# hyperion-rev2.net
KiCad netlist of a schematic drawn in EAGLE
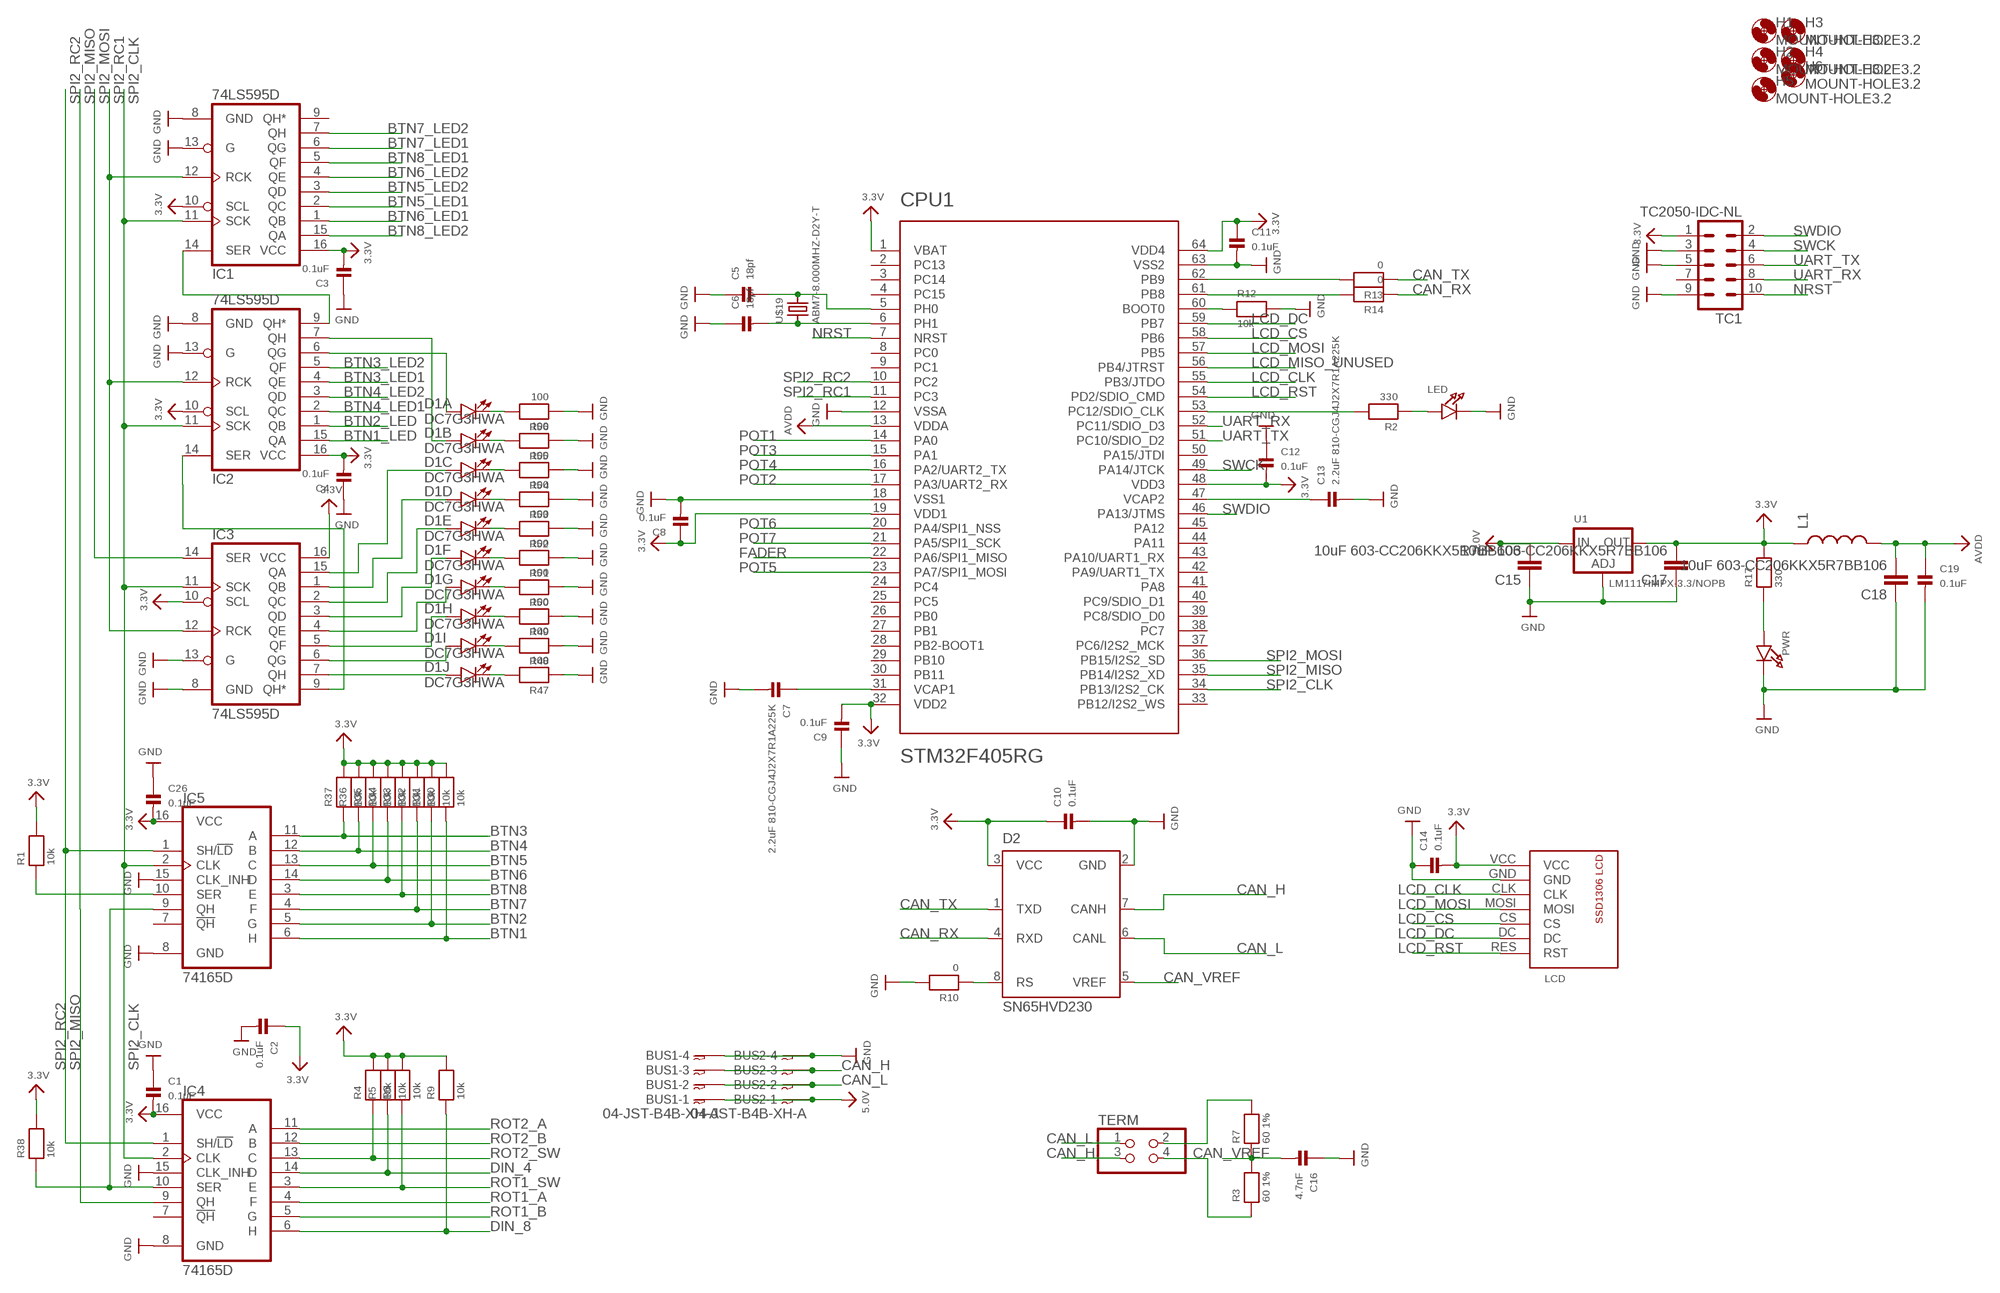
[diagram p0: schematic, sheet 1]
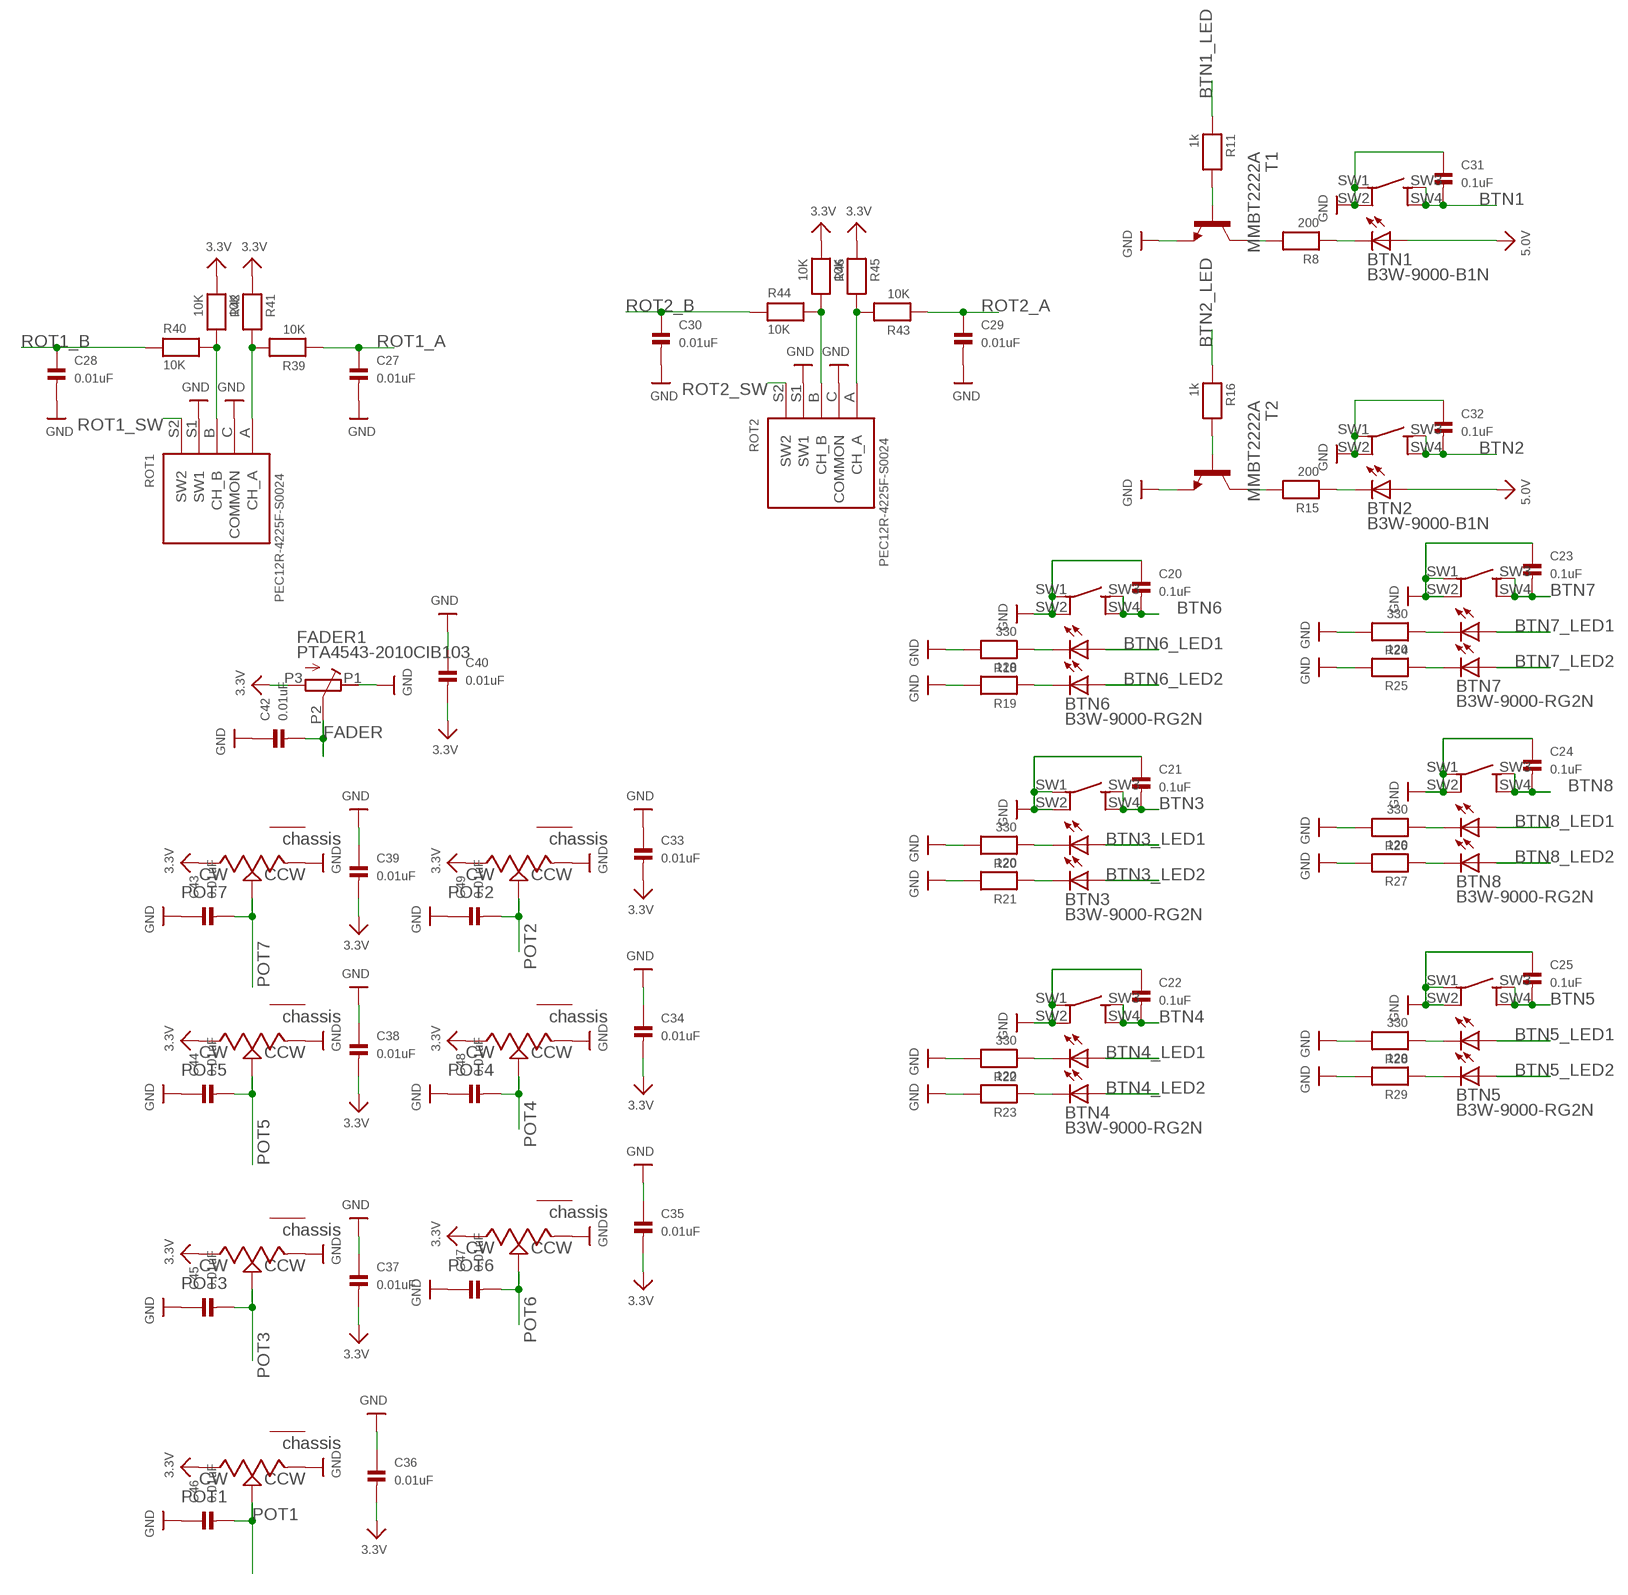
[diagram p1: schematic, sheet 2]

(export (version "E")
  (design (tool "Eeschema 10.0.6"))
  (components
    (comp (ref "BUS1")
      (value "04-JST-B4B-XH-A")
      (footprint "eagle-import:B4B-XH")
      (fields (field (name "MPN") "B4B-XH-A(LF)(SN)"))
      (libsource (lib "eagle-import") (part "04-JST-B4B-XH-A"))
    )
    (comp (ref "BUS2")
      (value "04-JST-B4B-XH-A")
      (footprint "eagle-import:B4B-XH")
      (fields (field (name "MPN") "B4B-XH-A(LF)(SN)"))
      (libsource (lib "eagle-import") (part "04-JST-B4B-XH-A"))
    )
    (comp (ref "C1")
      (value "0.1uF")
      (footprint "eagle-import:0603")
      (libsource (lib "eagle-import") (part "CAP_CERAMIC0603"))
    )
    (comp (ref "C2")
      (value "0.1uF")
      (footprint "eagle-import:0603")
      (libsource (lib "eagle-import") (part "CAP_CERAMIC0603"))
    )
    (comp (ref "C3")
      (value "0.1uF")
      (footprint "eagle-import:0603")
      (libsource (lib "eagle-import") (part "CAP_CERAMIC0603"))
    )
    (comp (ref "C4")
      (value "0.1uF")
      (footprint "eagle-import:0603")
      (libsource (lib "eagle-import") (part "CAP_CERAMIC0603"))
    )
    (comp (ref "C5")
      (value "18pf")
      (footprint "eagle-import:0603")
      (libsource (lib "eagle-import") (part "CAP_CERAMIC0603"))
    )
    (comp (ref "C6")
      (value "18pf")
      (footprint "eagle-import:0603")
      (libsource (lib "eagle-import") (part "CAP_CERAMIC0603"))
    )
    (comp (ref "C7")
      (value "2.2uF 810-CGJ4J2X7R1A225K")
      (footprint "eagle-import:0805")
      (fields (field (name "MPN") "CGJ4J2X7R1A225K125AA"))
      (libsource (lib "eagle-import") (part "CAP_CERAMIC0805"))
    )
    (comp (ref "C8")
      (value "0.1uF")
      (footprint "eagle-import:0603")
      (libsource (lib "eagle-import") (part "CAP_CERAMIC0603"))
    )
    (comp (ref "C9")
      (value "0.1uF")
      (footprint "eagle-import:0603")
      (libsource (lib "eagle-import") (part "CAP_CERAMIC0603"))
    )
    (comp (ref "C10")
      (value "0.1uF")
      (footprint "eagle-import:0603")
      (libsource (lib "eagle-import") (part "CAP_CERAMIC0603"))
    )
    (comp (ref "C11")
      (value "0.1uF")
      (footprint "eagle-import:0603")
      (libsource (lib "eagle-import") (part "CAP_CERAMIC0603"))
    )
    (comp (ref "C12")
      (value "0.1uF")
      (footprint "eagle-import:0603")
      (libsource (lib "eagle-import") (part "CAP_CERAMIC0603"))
    )
    (comp (ref "C13")
      (value "2.2uF 810-CGJ4J2X7R1A225K")
      (footprint "eagle-import:0805")
      (fields (field (name "MPN") "CGJ4J2X7R1A225K125AA"))
      (libsource (lib "eagle-import") (part "CAP_CERAMIC0805"))
    )
    (comp (ref "C14")
      (value "0.1uF")
      (footprint "eagle-import:0603")
      (libsource (lib "eagle-import") (part "CAP_CERAMIC0603"))
    )
    (comp (ref "C15")
      (value "10uF 603-CC206KKX5R7BB106")
      (footprint "eagle-import:1206")
      (fields (field (name "MPN") "CC1206KKX5R7BB106"))
      (libsource (lib "eagle-import") (part "CAP1206"))
    )
    (comp (ref "C16")
      (value "4.7nF")
      (footprint "eagle-import:0603")
      (libsource (lib "eagle-import") (part "CAP_CERAMIC0603"))
    )
    (comp (ref "C17")
      (value "10uF 603-CC206KKX5R7BB106")
      (footprint "eagle-import:1206")
      (fields (field (name "MPN") "CC1206KKX5R7BB106"))
      (libsource (lib "eagle-import") (part "CAP1206"))
    )
    (comp (ref "C18")
      (value "10uF 603-CC206KKX5R7BB106")
      (footprint "eagle-import:1206")
      (fields (field (name "MPN") "CC1206KKX5R7BB106"))
      (libsource (lib "eagle-import") (part "CAP1206"))
    )
    (comp (ref "C19")
      (value "0.1uF")
      (footprint "eagle-import:0603")
      (libsource (lib "eagle-import") (part "CAP_CERAMIC0603"))
    )
    (comp (ref "C26")
      (value "0.1uF")
      (footprint "eagle-import:0603")
      (libsource (lib "eagle-import") (part "CAP_CERAMIC0603"))
    )
    (comp (ref "CPU1")
      (value "STM32F405RG")
      (footprint "eagle-import:TQFP64")
      (fields (field (name "MPN") "STM32F405RGT6"))
      (libsource (lib "eagle-import") (part "STM32F405RG"))
    )
    (comp (ref "D1")
      (value "DC7G3HWA")
      (footprint "eagle-import:LED_BARGAPH_10")
      (libsource (lib "eagle-import") (part "LED_BARGRAPH_10"))
    )
    (comp (ref "D2")
      (value "SN65HVD230")
      (footprint "eagle-import:SO8")
      (fields (field (name "MPN") "SN65HVD230DR"))
      (libsource (lib "eagle-import") (part "SN65HVD230"))
    )
    (comp (ref "H1")
      (value "MOUNT-HOLE3.2")
      (footprint "eagle-import:3,2")
      (libsource (lib "eagle-import") (part "MOUNT-HOLE3.2"))
    )
    (comp (ref "H2")
      (value "MOUNT-HOLE3.2")
      (footprint "eagle-import:3,2")
      (libsource (lib "eagle-import") (part "MOUNT-HOLE3.2"))
    )
    (comp (ref "H3")
      (value "MOUNT-HOLE3.2")
      (footprint "eagle-import:3,2")
      (libsource (lib "eagle-import") (part "MOUNT-HOLE3.2"))
    )
    (comp (ref "H4")
      (value "MOUNT-HOLE3.2")
      (footprint "eagle-import:3,2")
      (libsource (lib "eagle-import") (part "MOUNT-HOLE3.2"))
    )
    (comp (ref "H5")
      (value "MOUNT-HOLE3.2")
      (footprint "eagle-import:3,2")
      (libsource (lib "eagle-import") (part "MOUNT-HOLE3.2"))
    )
    (comp (ref "H6")
      (value "MOUNT-HOLE3.2")
      (footprint "eagle-import:3,2")
      (libsource (lib "eagle-import") (part "MOUNT-HOLE3.2"))
    )
    (comp (ref "IC1")
      (value "74LS595D")
      (footprint "eagle-import:SO16")
      (fields (field (name "MPN") "74HC595D,118"))
      (libsource (lib "eagle-import") (part "74595DLS"))
    )
    (comp (ref "IC2")
      (value "74LS595D")
      (footprint "eagle-import:SO16")
      (fields (field (name "MPN") "74HC595D,118"))
      (libsource (lib "eagle-import") (part "74595DLS"))
    )
    (comp (ref "IC3")
      (value "74LS595D")
      (footprint "eagle-import:SO16")
      (fields (field (name "MPN") "74HC595D,118"))
      (libsource (lib "eagle-import") (part "74595DLS"))
    )
    (comp (ref "IC4")
      (value "74165D")
      (footprint "eagle-import:SO16")
      (fields (field (name "MPN") "74HC165D,653"))
      (libsource (lib "eagle-import") (part "74165D"))
    )
    (comp (ref "IC5")
      (value "74165D")
      (footprint "eagle-import:SO16")
      (fields (field (name "MPN") "74HC165D,653"))
      (libsource (lib "eagle-import") (part "74165D"))
    )
    (comp (ref "L1")
      (value "INDUCTOR0805")
      (footprint "eagle-import:0805")
      (fields (field (name "MPN") "2508056017Y2"))
      (libsource (lib "eagle-import") (part "INDUCTOR0805"))
    )
    (comp (ref "LCD")
      (value "SSD1306-7PINWITHOUT-HOLES")
      (footprint "eagle-import:SSD1306-7PIN-NO-HOLES")
      (libsource (lib "eagle-import") (part "SSD1306-7PINWITHOUT-HOLES"))
    )
    (comp (ref "LED")
      (value "LED0603")
      (footprint "eagle-import:CHIPLED_0603")
      (fields (field (name "MPN") "MF-LED-0603-GREEN"))
      (libsource (lib "eagle-import") (part "LED0603"))
    )
    (comp (ref "PWR")
      (value "LED0603")
      (footprint "eagle-import:CHIPLED_0603")
      (fields (field (name "MPN") "MF-LED-0603-GREEN"))
      (libsource (lib "eagle-import") (part "LED0603"))
    )
    (comp (ref "R1")
      (value "10k")
      (footprint "eagle-import:_0603")
      (libsource (lib "eagle-import") (part "RESISTOR_0603"))
    )
    (comp (ref "R2")
      (value "330")
      (footprint "eagle-import:0603")
      (libsource (lib "eagle-import") (part "RESISTOR0603"))
    )
    (comp (ref "R3")
      (value "60 1%")
      (footprint "eagle-import:0603")
      (fields (field (name "MPN") "MF-RES-0603-60.4"))
      (libsource (lib "eagle-import") (part "RESISTOR0603"))
    )
    (comp (ref "R4")
      (value "10k")
      (footprint "eagle-import:_0603")
      (libsource (lib "eagle-import") (part "RESISTOR_0603"))
    )
    (comp (ref "R5")
      (value "10k")
      (footprint "eagle-import:_0603")
      (libsource (lib "eagle-import") (part "RESISTOR_0603"))
    )
    (comp (ref "R6")
      (value "10k")
      (footprint "eagle-import:_0603")
      (libsource (lib "eagle-import") (part "RESISTOR_0603"))
    )
    (comp (ref "R7")
      (value "60 1%")
      (footprint "eagle-import:0603")
      (fields (field (name "MPN") "MF-RES-0603-60.4"))
      (libsource (lib "eagle-import") (part "RESISTOR0603"))
    )
    (comp (ref "R9")
      (value "10k")
      (footprint "eagle-import:_0603")
      (libsource (lib "eagle-import") (part "RESISTOR_0603"))
    )
    (comp (ref "R10")
      (value "0")
      (footprint "eagle-import:_0603")
      (libsource (lib "eagle-import") (part "RESISTOR_0603"))
    )
    (comp (ref "R12")
      (value "10k")
      (footprint "eagle-import:_0603")
      (libsource (lib "eagle-import") (part "RESISTOR_0603"))
    )
    (comp (ref "R13")
      (value "0")
      (footprint "eagle-import:_0603")
      (libsource (lib "eagle-import") (part "RESISTOR_0603"))
    )
    (comp (ref "R14")
      (value "0")
      (footprint "eagle-import:_0603")
      (libsource (lib "eagle-import") (part "RESISTOR_0603"))
    )
    (comp (ref "R17")
      (value "330")
      (footprint "eagle-import:0603")
      (libsource (lib "eagle-import") (part "RESISTOR0603"))
    )
    (comp (ref "R30")
      (value "10k")
      (footprint "eagle-import:_0603")
      (libsource (lib "eagle-import") (part "RESISTOR_0603"))
    )
    (comp (ref "R31")
      (value "10k")
      (footprint "eagle-import:_0603")
      (libsource (lib "eagle-import") (part "RESISTOR_0603"))
    )
    (comp (ref "R32")
      (value "10k")
      (footprint "eagle-import:_0603")
      (libsource (lib "eagle-import") (part "RESISTOR_0603"))
    )
    (comp (ref "R33")
      (value "10k")
      (footprint "eagle-import:_0603")
      (libsource (lib "eagle-import") (part "RESISTOR_0603"))
    )
    (comp (ref "R34")
      (value "10k")
      (footprint "eagle-import:_0603")
      (libsource (lib "eagle-import") (part "RESISTOR_0603"))
    )
    (comp (ref "R35")
      (value "10k")
      (footprint "eagle-import:_0603")
      (libsource (lib "eagle-import") (part "RESISTOR_0603"))
    )
    (comp (ref "R36")
      (value "10k")
      (footprint "eagle-import:_0603")
      (libsource (lib "eagle-import") (part "RESISTOR_0603"))
    )
    (comp (ref "R37")
      (value "10k")
      (footprint "eagle-import:_0603")
      (libsource (lib "eagle-import") (part "RESISTOR_0603"))
    )
    (comp (ref "R38")
      (value "10k")
      (footprint "eagle-import:_0603")
      (libsource (lib "eagle-import") (part "RESISTOR_0603"))
    )
    (comp (ref "R47")
      (value "100")
      (footprint "eagle-import:_0603")
      (libsource (lib "eagle-import") (part "RESISTOR_0603"))
    )
    (comp (ref "R48")
      (value "100")
      (footprint "eagle-import:_0603")
      (libsource (lib "eagle-import") (part "RESISTOR_0603"))
    )
    (comp (ref "R49")
      (value "100")
      (footprint "eagle-import:_0603")
      (libsource (lib "eagle-import") (part "RESISTOR_0603"))
    )
    (comp (ref "R50")
      (value "100")
      (footprint "eagle-import:_0603")
      (libsource (lib "eagle-import") (part "RESISTOR_0603"))
    )
    (comp (ref "R51")
      (value "100")
      (footprint "eagle-import:_0603")
      (libsource (lib "eagle-import") (part "RESISTOR_0603"))
    )
    (comp (ref "R52")
      (value "100")
      (footprint "eagle-import:_0603")
      (libsource (lib "eagle-import") (part "RESISTOR_0603"))
    )
    (comp (ref "R53")
      (value "100")
      (footprint "eagle-import:_0603")
      (libsource (lib "eagle-import") (part "RESISTOR_0603"))
    )
    (comp (ref "R54")
      (value "100")
      (footprint "eagle-import:_0603")
      (libsource (lib "eagle-import") (part "RESISTOR_0603"))
    )
    (comp (ref "R55")
      (value "100")
      (footprint "eagle-import:_0603")
      (libsource (lib "eagle-import") (part "RESISTOR_0603"))
    )
    (comp (ref "R56")
      (value "100")
      (footprint "eagle-import:_0603")
      (libsource (lib "eagle-import") (part "RESISTOR_0603"))
    )
    (comp (ref "TC1")
      (value "TC2050-IDC-NL")
      (footprint "eagle-import:TC2050-IDC-NL")
      (libsource (lib "eagle-import") (part "TC2050-IDC-NL"))
    )
    (comp (ref "TERM")
      (value "PINHD-2X2")
      (footprint "eagle-import:2X02")
      (fields (field (name "MPN") "5-146254-2"))
      (libsource (lib "eagle-import") (part "PINHD-2X2"))
    )
    (comp (ref "U$19")
      (value "ABM7-8.000MHZ-D2Y-T")
      (footprint "eagle-import:ABM7-8.000MHZ-D2Y-T")
      (libsource (lib "eagle-import") (part "ABM7-8.000MHZ-D2Y-T"))
    )
    (comp (ref "U1")
      (value "LM1117IMPX-3.3/NOPB")
      (footprint "eagle-import:SOT223-R")
      (fields (field (name "MPN") "LM1117MPX-3.3/NOPB"))
      (libsource (lib "eagle-import") (part "LM1117SOT223-REFLOW"))
    )
    (comp (ref "BTN1")
      (value "B3W-9000-B1N")
      (footprint "eagle-import:B3W-9000-X1X")
      (libsource (lib "eagle-import") (part "B3W-9000-B1N"))
    )
    (comp (ref "BTN2")
      (value "B3W-9000-B1N")
      (footprint "eagle-import:B3W-9000-X1X")
      (libsource (lib "eagle-import") (part "B3W-9000-B1N"))
    )
    (comp (ref "BTN3")
      (value "B3W-9000-RG2N")
      (footprint "eagle-import:B3W-9000-X2X")
      (libsource (lib "eagle-import") (part "B3W-9000-RG2N"))
    )
    (comp (ref "BTN4")
      (value "B3W-9000-RG2N")
      (footprint "eagle-import:B3W-9000-X2X")
      (libsource (lib "eagle-import") (part "B3W-9000-RG2N"))
    )
    (comp (ref "BTN5")
      (value "B3W-9000-RG2N")
      (footprint "eagle-import:B3W-9000-X2X")
      (libsource (lib "eagle-import") (part "B3W-9000-RG2N"))
    )
    (comp (ref "BTN6")
      (value "B3W-9000-RG2N")
      (footprint "eagle-import:B3W-9000-X2X")
      (libsource (lib "eagle-import") (part "B3W-9000-RG2N"))
    )
    (comp (ref "BTN7")
      (value "B3W-9000-RG2N")
      (footprint "eagle-import:B3W-9000-X2X")
      (libsource (lib "eagle-import") (part "B3W-9000-RG2N"))
    )
    (comp (ref "BTN8")
      (value "B3W-9000-RG2N")
      (footprint "eagle-import:B3W-9000-X2X")
      (libsource (lib "eagle-import") (part "B3W-9000-RG2N"))
    )
    (comp (ref "C20")
      (value "0.1uF")
      (footprint "eagle-import:0603")
      (libsource (lib "eagle-import") (part "CAP_CERAMIC0603"))
    )
    (comp (ref "C21")
      (value "0.1uF")
      (footprint "eagle-import:0603")
      (libsource (lib "eagle-import") (part "CAP_CERAMIC0603"))
    )
    (comp (ref "C22")
      (value "0.1uF")
      (footprint "eagle-import:0603")
      (libsource (lib "eagle-import") (part "CAP_CERAMIC0603"))
    )
    (comp (ref "C23")
      (value "0.1uF")
      (footprint "eagle-import:0603")
      (libsource (lib "eagle-import") (part "CAP_CERAMIC0603"))
    )
    (comp (ref "C24")
      (value "0.1uF")
      (footprint "eagle-import:0603")
      (libsource (lib "eagle-import") (part "CAP_CERAMIC0603"))
    )
    (comp (ref "C25")
      (value "0.1uF")
      (footprint "eagle-import:0603")
      (libsource (lib "eagle-import") (part "CAP_CERAMIC0603"))
    )
    (comp (ref "C27")
      (value "0.01uF")
      (footprint "eagle-import:0603")
      (libsource (lib "eagle-import") (part "CAP_CERAMIC0603"))
    )
    (comp (ref "C28")
      (value "0.01uF")
      (footprint "eagle-import:0603")
      (libsource (lib "eagle-import") (part "CAP_CERAMIC0603"))
    )
    (comp (ref "C29")
      (value "0.01uF")
      (footprint "eagle-import:0603")
      (libsource (lib "eagle-import") (part "CAP_CERAMIC0603"))
    )
    (comp (ref "C30")
      (value "0.01uF")
      (footprint "eagle-import:0603")
      (libsource (lib "eagle-import") (part "CAP_CERAMIC0603"))
    )
    (comp (ref "C31")
      (value "0.1uF")
      (footprint "eagle-import:0603")
      (libsource (lib "eagle-import") (part "CAP_CERAMIC0603"))
    )
    (comp (ref "C32")
      (value "0.1uF")
      (footprint "eagle-import:0603")
      (libsource (lib "eagle-import") (part "CAP_CERAMIC0603"))
    )
    (comp (ref "C33")
      (value "0.01uF")
      (footprint "eagle-import:0603")
      (libsource (lib "eagle-import") (part "CAP_CERAMIC0603"))
    )
    (comp (ref "C34")
      (value "0.01uF")
      (footprint "eagle-import:0603")
      (libsource (lib "eagle-import") (part "CAP_CERAMIC0603"))
    )
    (comp (ref "C35")
      (value "0.01uF")
      (footprint "eagle-import:0603")
      (libsource (lib "eagle-import") (part "CAP_CERAMIC0603"))
    )
    (comp (ref "C36")
      (value "0.01uF")
      (footprint "eagle-import:0603")
      (libsource (lib "eagle-import") (part "CAP_CERAMIC0603"))
    )
    (comp (ref "C37")
      (value "0.01uF")
      (footprint "eagle-import:0603")
      (libsource (lib "eagle-import") (part "CAP_CERAMIC0603"))
    )
    (comp (ref "C38")
      (value "0.01uF")
      (footprint "eagle-import:0603")
      (libsource (lib "eagle-import") (part "CAP_CERAMIC0603"))
    )
    (comp (ref "C39")
      (value "0.01uF")
      (footprint "eagle-import:0603")
      (libsource (lib "eagle-import") (part "CAP_CERAMIC0603"))
    )
    (comp (ref "C40")
      (value "0.01uF")
      (footprint "eagle-import:0603")
      (libsource (lib "eagle-import") (part "CAP_CERAMIC0603"))
    )
    (comp (ref "C42")
      (value "0.01uF")
      (footprint "eagle-import:0603")
      (libsource (lib "eagle-import") (part "CAP_CERAMIC0603"))
    )
    (comp (ref "C43")
      (value "0.01uF")
      (footprint "eagle-import:0603")
      (libsource (lib "eagle-import") (part "CAP_CERAMIC0603"))
    )
    (comp (ref "C44")
      (value "0.01uF")
      (footprint "eagle-import:0603")
      (libsource (lib "eagle-import") (part "CAP_CERAMIC0603"))
    )
    (comp (ref "C45")
      (value "0.01uF")
      (footprint "eagle-import:0603")
      (libsource (lib "eagle-import") (part "CAP_CERAMIC0603"))
    )
    (comp (ref "C46")
      (value "0.01uF")
      (footprint "eagle-import:0603")
      (libsource (lib "eagle-import") (part "CAP_CERAMIC0603"))
    )
    (comp (ref "C47")
      (value "0.01uF")
      (footprint "eagle-import:0603")
      (libsource (lib "eagle-import") (part "CAP_CERAMIC0603"))
    )
    (comp (ref "C48")
      (value "0.01uF")
      (footprint "eagle-import:0603")
      (libsource (lib "eagle-import") (part "CAP_CERAMIC0603"))
    )
    (comp (ref "C49")
      (value "0.01uF")
      (footprint "eagle-import:0603")
      (libsource (lib "eagle-import") (part "CAP_CERAMIC0603"))
    )
    (comp (ref "FADER1")
      (value "PTA4543-2010CIB103")
      (footprint "eagle-import:PTA4543-2015CPB103")
      (libsource (lib "eagle-import") (part "PTA4543-2015CPB103"))
    )
    (comp (ref "POT1")
      (value "POTENTIOMETERPTV09A_VERTICAL")
      (footprint "eagle-import:PTV09A-4")
      (fields (field (name "MPN") "PTV09A-4225F-B203"))
      (libsource (lib "eagle-import") (part "POTENTIOMETERPTV09A_VERTICAL"))
    )
    (comp (ref "POT2")
      (value "POTENTIOMETERPTV09A_VERTICAL")
      (footprint "eagle-import:PTV09A-4")
      (fields (field (name "MPN") "PTV09A-4225F-B203"))
      (libsource (lib "eagle-import") (part "POTENTIOMETERPTV09A_VERTICAL"))
    )
    (comp (ref "POT3")
      (value "POTENTIOMETERPTV09A_VERTICAL")
      (footprint "eagle-import:PTV09A-4")
      (fields (field (name "MPN") "PTV09A-4225F-B203"))
      (libsource (lib "eagle-import") (part "POTENTIOMETERPTV09A_VERTICAL"))
    )
    (comp (ref "POT4")
      (value "POTENTIOMETERPTV09A_VERTICAL")
      (footprint "eagle-import:PTV09A-4")
      (fields (field (name "MPN") "PTV09A-4225F-B203"))
      (libsource (lib "eagle-import") (part "POTENTIOMETERPTV09A_VERTICAL"))
    )
    (comp (ref "POT5")
      (value "POTENTIOMETERPTV09A_VERTICAL")
      (footprint "eagle-import:PTV09A-4")
      (fields (field (name "MPN") "PTV09A-4225F-B203"))
      (libsource (lib "eagle-import") (part "POTENTIOMETERPTV09A_VERTICAL"))
    )
    (comp (ref "POT6")
      (value "POTENTIOMETERPTV09A_VERTICAL")
      (footprint "eagle-import:PTV09A-4")
      (fields (field (name "MPN") "PTV09A-4225F-B203"))
      (libsource (lib "eagle-import") (part "POTENTIOMETERPTV09A_VERTICAL"))
    )
    (comp (ref "POT7")
      (value "POTENTIOMETERPTV09A_VERTICAL")
      (footprint "eagle-import:PTV09A-4")
      (fields (field (name "MPN") "PTV09A-4225F-B203"))
      (libsource (lib "eagle-import") (part "POTENTIOMETERPTV09A_VERTICAL"))
    )
    (comp (ref "R8")
      (value "200")
      (footprint "eagle-import:0603")
      (libsource (lib "eagle-import") (part "RESISTOR0603"))
    )
    (comp (ref "R11")
      (value "1k")
      (footprint "eagle-import:0603")
      (libsource (lib "eagle-import") (part "RESISTOR0603"))
    )
    (comp (ref "R15")
      (value "200")
      (footprint "eagle-import:0603")
      (libsource (lib "eagle-import") (part "RESISTOR0603"))
    )
    (comp (ref "R16")
      (value "1k")
      (footprint "eagle-import:0603")
      (libsource (lib "eagle-import") (part "RESISTOR0603"))
    )
    (comp (ref "R18")
      (value "330")
      (footprint "eagle-import:0603")
      (libsource (lib "eagle-import") (part "RESISTOR0603"))
    )
    (comp (ref "R19")
      (value "120")
      (footprint "eagle-import:0603")
      (libsource (lib "eagle-import") (part "RESISTOR0603"))
    )
    (comp (ref "R20")
      (value "330")
      (footprint "eagle-import:0603")
      (libsource (lib "eagle-import") (part "RESISTOR0603"))
    )
    (comp (ref "R21")
      (value "120")
      (footprint "eagle-import:0603")
      (libsource (lib "eagle-import") (part "RESISTOR0603"))
    )
    (comp (ref "R22")
      (value "330")
      (footprint "eagle-import:0603")
      (libsource (lib "eagle-import") (part "RESISTOR0603"))
    )
    (comp (ref "R23")
      (value "120")
      (footprint "eagle-import:0603")
      (libsource (lib "eagle-import") (part "RESISTOR0603"))
    )
    (comp (ref "R24")
      (value "330")
      (footprint "eagle-import:0603")
      (libsource (lib "eagle-import") (part "RESISTOR0603"))
    )
    (comp (ref "R25")
      (value "120")
      (footprint "eagle-import:0603")
      (libsource (lib "eagle-import") (part "RESISTOR0603"))
    )
    (comp (ref "R26")
      (value "330")
      (footprint "eagle-import:0603")
      (libsource (lib "eagle-import") (part "RESISTOR0603"))
    )
    (comp (ref "R27")
      (value "120")
      (footprint "eagle-import:0603")
      (libsource (lib "eagle-import") (part "RESISTOR0603"))
    )
    (comp (ref "R28")
      (value "330")
      (footprint "eagle-import:0603")
      (libsource (lib "eagle-import") (part "RESISTOR0603"))
    )
    (comp (ref "R29")
      (value "120")
      (footprint "eagle-import:0603")
      (libsource (lib "eagle-import") (part "RESISTOR0603"))
    )
    (comp (ref "R39")
      (value "10K")
      (footprint "eagle-import:0603")
      (libsource (lib "eagle-import") (part "RESISTOR0603"))
    )
    (comp (ref "R40")
      (value "10K")
      (footprint "eagle-import:0603")
      (libsource (lib "eagle-import") (part "RESISTOR0603"))
    )
    (comp (ref "R41")
      (value "10K")
      (footprint "eagle-import:0603")
      (libsource (lib "eagle-import") (part "RESISTOR0603"))
    )
    (comp (ref "R42")
      (value "10K")
      (footprint "eagle-import:0603")
      (libsource (lib "eagle-import") (part "RESISTOR0603"))
    )
    (comp (ref "R43")
      (value "10K")
      (footprint "eagle-import:0603")
      (libsource (lib "eagle-import") (part "RESISTOR0603"))
    )
    (comp (ref "R44")
      (value "10K")
      (footprint "eagle-import:0603")
      (libsource (lib "eagle-import") (part "RESISTOR0603"))
    )
    (comp (ref "R45")
      (value "10K")
      (footprint "eagle-import:0603")
      (libsource (lib "eagle-import") (part "RESISTOR0603"))
    )
    (comp (ref "R46")
      (value "10K")
      (footprint "eagle-import:0603")
      (libsource (lib "eagle-import") (part "RESISTOR0603"))
    )
    (comp (ref "ROT1")
      (value "PEC12R-4225F-S0024")
      (footprint "eagle-import:PEC111-4XXXK-SXXXX")
      (libsource (lib "eagle-import") (part "PEC11-4215K-S0024"))
    )
    (comp (ref "ROT2")
      (value "PEC12R-4225F-S0024")
      (footprint "eagle-import:PEC111-4XXXK-SXXXX")
      (libsource (lib "eagle-import") (part "PEC11-4215K-S0024"))
    )
    (comp (ref "T1")
      (value "MMBT2222A")
      (footprint "eagle-import:SOT23-BEC")
      (libsource (lib "eagle-import") (part "-NPN-SOT23-BECMMBT2222ALT1"))
    )
    (comp (ref "T2")
      (value "MMBT2222A")
      (footprint "eagle-import:SOT23-BEC")
      (libsource (lib "eagle-import") (part "-NPN-SOT23-BECMMBT2222ALT1"))
    )
  )
  (nets
    (net (code "1") (name "3.3V") (class "Default")
      (node (ref "C1") (pin "2") (pinfunction "P$2_2") (pintype "passive"))
      (node (ref "C10") (pin "1") (pinfunction "P$1_1") (pintype "passive"))
      (node (ref "C11") (pin "1") (pinfunction "P$1_1") (pintype "passive"))
      (node (ref "C12") (pin "2") (pinfunction "P$2_2") (pintype "passive"))
      (node (ref "C14") (pin "2") (pinfunction "P$2_2") (pintype "passive"))
      (node (ref "C17") (pin "2") (pinfunction "2_2") (pintype "passive"))
      (node (ref "C2") (pin "1") (pinfunction "P$1_1") (pintype "passive"))
      (node (ref "C26") (pin "2") (pinfunction "P$2_2") (pintype "passive"))
      (node (ref "C3") (pin "2") (pinfunction "P$2_2") (pintype "passive"))
      (node (ref "C33") (pin "2") (pinfunction "P$2_2") (pintype "passive"))
      (node (ref "C34") (pin "2") (pinfunction "P$2_2") (pintype "passive"))
      (node (ref "C35") (pin "2") (pinfunction "P$2_2") (pintype "passive"))
      (node (ref "C36") (pin "2") (pinfunction "P$2_2") (pintype "passive"))
      (node (ref "C37") (pin "2") (pinfunction "P$2_2") (pintype "passive"))
      (node (ref "C38") (pin "2") (pinfunction "P$2_2") (pintype "passive"))
      (node (ref "C39") (pin "2") (pinfunction "P$2_2") (pintype "passive"))
      (node (ref "C4") (pin "2") (pinfunction "P$2_2") (pintype "passive"))
      (node (ref "C40") (pin "2") (pinfunction "P$2_2") (pintype "passive"))
      (node (ref "C8") (pin "1") (pinfunction "P$1_1") (pintype "passive"))
      (node (ref "C9") (pin "2") (pinfunction "P$2_2") (pintype "passive"))
      (node (ref "CPU1") (pin "1") (pinfunction "VBAT_1") (pintype "bidirectional"))
      (node (ref "CPU1") (pin "19") (pinfunction "VDD1_19") (pintype "bidirectional"))
      (node (ref "CPU1") (pin "32") (pinfunction "VDD2_32") (pintype "bidirectional"))
      (node (ref "CPU1") (pin "48") (pinfunction "VDD3_48") (pintype "bidirectional"))
      (node (ref "CPU1") (pin "64") (pinfunction "VDD4_64") (pintype "bidirectional"))
      (node (ref "D2") (pin "3") (pinfunction "VCC_3") (pintype "power_in"))
      (node (ref "FADER1") (pin "P3") (pinfunction "E_P3") (pintype "passive"))
      (node (ref "IC1") (pin "10") (pinfunction "SCL_10") (pintype "input"))
      (node (ref "IC1") (pin "16") (pinfunction "VCC_16") (pintype "power_in"))
      (node (ref "IC2") (pin "10") (pinfunction "SCL_10") (pintype "input"))
      (node (ref "IC2") (pin "16") (pinfunction "VCC_16") (pintype "power_in"))
      (node (ref "IC3") (pin "10") (pinfunction "SCL_10") (pintype "input"))
      (node (ref "IC3") (pin "16") (pinfunction "VCC_16") (pintype "power_in"))
      (node (ref "IC4") (pin "16") (pinfunction "VCC_16") (pintype "power_in"))
      (node (ref "IC5") (pin "16") (pinfunction "VCC_16") (pintype "power_in"))
      (node (ref "L1") (pin "1") (pinfunction "1_1") (pintype "passive"))
      (node (ref "LCD") (pin "VCC") (pinfunction "VCC_VCC") (pintype "bidirectional"))
      (node (ref "POT1") (pin "CW") (pinfunction "CW_CW") (pintype "passive"))
      (node (ref "POT2") (pin "CW") (pinfunction "CW_CW") (pintype "passive"))
      (node (ref "POT3") (pin "CW") (pinfunction "CW_CW") (pintype "passive"))
      (node (ref "POT4") (pin "CW") (pinfunction "CW_CW") (pintype "passive"))
      (node (ref "POT5") (pin "CW") (pinfunction "CW_CW") (pintype "passive"))
      (node (ref "POT6") (pin "CW") (pinfunction "CW_CW") (pintype "passive"))
      (node (ref "POT7") (pin "CW") (pinfunction "CW_CW") (pintype "passive"))
      (node (ref "R1") (pin "2") (pinfunction "2_2") (pintype "passive"))
      (node (ref "R17") (pin "2") (pinfunction "2_2") (pintype "passive"))
      (node (ref "R30") (pin "2") (pinfunction "2_2") (pintype "passive"))
      (node (ref "R31") (pin "2") (pinfunction "2_2") (pintype "passive"))
      (node (ref "R32") (pin "2") (pinfunction "2_2") (pintype "passive"))
      (node (ref "R33") (pin "2") (pinfunction "2_2") (pintype "passive"))
      (node (ref "R34") (pin "2") (pinfunction "2_2") (pintype "passive"))
      (node (ref "R35") (pin "2") (pinfunction "2_2") (pintype "passive"))
      (node (ref "R36") (pin "2") (pinfunction "2_2") (pintype "passive"))
      (node (ref "R37") (pin "2") (pinfunction "2_2") (pintype "passive"))
      (node (ref "R38") (pin "2") (pinfunction "2_2") (pintype "passive"))
      (node (ref "R4") (pin "2") (pinfunction "2_2") (pintype "passive"))
      (node (ref "R41") (pin "1") (pinfunction "1_1") (pintype "passive"))
      (node (ref "R42") (pin "1") (pinfunction "1_1") (pintype "passive"))
      (node (ref "R45") (pin "1") (pinfunction "1_1") (pintype "passive"))
      (node (ref "R46") (pin "1") (pinfunction "1_1") (pintype "passive"))
      (node (ref "R5") (pin "2") (pinfunction "2_2") (pintype "passive"))
      (node (ref "R6") (pin "2") (pinfunction "2_2") (pintype "passive"))
      (node (ref "R9") (pin "2") (pinfunction "2_2") (pintype "passive"))
      (node (ref "TC1") (pin "1") (pinfunction "1_1") (pintype "passive"))
      (node (ref "U1") (pin "2") (pinfunction "OUT_2") (pintype "passive"))
    )
    (net (code "2") (name "5.0V") (class "Default")
      (node (ref "BTN1") (pin "LED1+") (pinfunction "LED1+_LED1+") (pintype "passive"))
      (node (ref "BTN2") (pin "LED1+") (pinfunction "LED1+_LED1+") (pintype "passive"))
      (node (ref "BUS1") (pin "P$1") (pinfunction "1_P$1") (pintype "passive"))
      (node (ref "BUS2") (pin "P$1") (pinfunction "1_P$1") (pintype "passive"))
      (node (ref "C15") (pin "2") (pinfunction "2_2") (pintype "passive"))
      (node (ref "U1") (pin "3") (pinfunction "IN_3") (pintype "input"))
    )
    (net (code "3") (name "AVDD") (class "Default")
      (node (ref "C18") (pin "2") (pinfunction "2_2") (pintype "passive"))
      (node (ref "C19") (pin "1") (pinfunction "P$1_1") (pintype "passive"))
      (node (ref "CPU1") (pin "13") (pinfunction "VDDA_13") (pintype "bidirectional"))
      (node (ref "L1") (pin "2") (pinfunction "2_2") (pintype "passive"))
    )
    (net (code "4") (name "BTN1") (class "Default")
      (node (ref "BTN1") (pin "SW3") (pinfunction "SW2_A_SW3") (pintype "passive"))
      (node (ref "BTN1") (pin "SW4") (pinfunction "SW2_B_SW4") (pintype "passive"))
      (node (ref "C31") (pin "2") (pinfunction "P$2_2") (pintype "passive"))
      (node (ref "IC5") (pin "6") (pinfunction "H_6") (pintype "tri_state"))
      (node (ref "R30") (pin "1") (pinfunction "1_1") (pintype "passive"))
    )
    (net (code "5") (name "BTN1_LED") (class "Default")
      (node (ref "IC2") (pin "15") (pinfunction "QA_15") (pintype "tri_state"))
      (node (ref "R11") (pin "1") (pinfunction "1_1") (pintype "passive"))
    )
    (net (code "6") (name "BTN2") (class "Default")
      (node (ref "BTN2") (pin "SW3") (pinfunction "SW2_A_SW3") (pintype "passive"))
      (node (ref "BTN2") (pin "SW4") (pinfunction "SW2_B_SW4") (pintype "passive"))
      (node (ref "C32") (pin "2") (pinfunction "P$2_2") (pintype "passive"))
      (node (ref "IC5") (pin "5") (pinfunction "G_5") (pintype "tri_state"))
      (node (ref "R31") (pin "1") (pinfunction "1_1") (pintype "passive"))
    )
    (net (code "7") (name "BTN2_LED") (class "Default")
      (node (ref "IC2") (pin "1") (pinfunction "QB_1") (pintype "tri_state"))
      (node (ref "R16") (pin "1") (pinfunction "1_1") (pintype "passive"))
    )
    (net (code "8") (name "BTN3") (class "Default")
      (node (ref "BTN3") (pin "SW3") (pinfunction "SW2_A_SW3") (pintype "passive"))
      (node (ref "BTN3") (pin "SW4") (pinfunction "SW2_B_SW4") (pintype "passive"))
      (node (ref "C21") (pin "2") (pinfunction "P$2_2") (pintype "passive"))
      (node (ref "IC5") (pin "11") (pinfunction "A_11") (pintype "tri_state"))
      (node (ref "R37") (pin "1") (pinfunction "1_1") (pintype "passive"))
    )
    (net (code "9") (name "BTN3_LED1") (class "Default")
      (node (ref "BTN3") (pin "LED1+") (pinfunction "LED1+_LED1+") (pintype "passive"))
      (node (ref "IC2") (pin "4") (pinfunction "QE_4") (pintype "tri_state"))
    )
    (net (code "10") (name "BTN3_LED2") (class "Default")
      (node (ref "BTN3") (pin "LED2+") (pinfunction "LED2+_LED2+") (pintype "passive"))
      (node (ref "IC2") (pin "5") (pinfunction "QF_5") (pintype "tri_state"))
    )
    (net (code "11") (name "BTN4") (class "Default")
      (node (ref "BTN4") (pin "SW3") (pinfunction "SW2_A_SW3") (pintype "passive"))
      (node (ref "BTN4") (pin "SW4") (pinfunction "SW2_B_SW4") (pintype "passive"))
      (node (ref "C22") (pin "2") (pinfunction "P$2_2") (pintype "passive"))
      (node (ref "IC5") (pin "12") (pinfunction "B_12") (pintype "tri_state"))
      (node (ref "R36") (pin "1") (pinfunction "1_1") (pintype "passive"))
    )
    (net (code "12") (name "BTN4_LED1") (class "Default")
      (node (ref "BTN4") (pin "LED1+") (pinfunction "LED1+_LED1+") (pintype "passive"))
      (node (ref "IC2") (pin "2") (pinfunction "QC_2") (pintype "tri_state"))
    )
    (net (code "13") (name "BTN4_LED2") (class "Default")
      (node (ref "BTN4") (pin "LED2+") (pinfunction "LED2+_LED2+") (pintype "passive"))
      (node (ref "IC2") (pin "3") (pinfunction "QD_3") (pintype "tri_state"))
    )
    (net (code "14") (name "BTN5") (class "Default")
      (node (ref "BTN5") (pin "SW3") (pinfunction "SW2_A_SW3") (pintype "passive"))
      (node (ref "BTN5") (pin "SW4") (pinfunction "SW2_B_SW4") (pintype "passive"))
      (node (ref "C25") (pin "2") (pinfunction "P$2_2") (pintype "passive"))
      (node (ref "IC5") (pin "13") (pinfunction "C_13") (pintype "tri_state"))
      (node (ref "R35") (pin "1") (pinfunction "1_1") (pintype "passive"))
    )
    (net (code "15") (name "BTN5_LED1") (class "Default")
      (node (ref "BTN5") (pin "LED1+") (pinfunction "LED1+_LED1+") (pintype "passive"))
      (node (ref "IC1") (pin "2") (pinfunction "QC_2") (pintype "tri_state"))
    )
    (net (code "16") (name "BTN5_LED2") (class "Default")
      (node (ref "BTN5") (pin "LED2+") (pinfunction "LED2+_LED2+") (pintype "passive"))
      (node (ref "IC1") (pin "3") (pinfunction "QD_3") (pintype "tri_state"))
    )
    (net (code "17") (name "BTN6") (class "Default")
      (node (ref "BTN6") (pin "SW3") (pinfunction "SW2_A_SW3") (pintype "passive"))
      (node (ref "BTN6") (pin "SW4") (pinfunction "SW2_B_SW4") (pintype "passive"))
      (node (ref "C20") (pin "2") (pinfunction "P$2_2") (pintype "passive"))
      (node (ref "IC5") (pin "14") (pinfunction "D_14") (pintype "tri_state"))
      (node (ref "R34") (pin "1") (pinfunction "1_1") (pintype "passive"))
    )
    (net (code "18") (name "BTN6_LED1") (class "Default")
      (node (ref "BTN6") (pin "LED1+") (pinfunction "LED1+_LED1+") (pintype "passive"))
      (node (ref "IC1") (pin "1") (pinfunction "QB_1") (pintype "tri_state"))
    )
    (net (code "19") (name "BTN6_LED2") (class "Default")
      (node (ref "BTN6") (pin "LED2+") (pinfunction "LED2+_LED2+") (pintype "passive"))
      (node (ref "IC1") (pin "4") (pinfunction "QE_4") (pintype "tri_state"))
    )
    (net (code "20") (name "BTN7") (class "Default")
      (node (ref "BTN7") (pin "SW3") (pinfunction "SW2_A_SW3") (pintype "passive"))
      (node (ref "BTN7") (pin "SW4") (pinfunction "SW2_B_SW4") (pintype "passive"))
      (node (ref "C23") (pin "2") (pinfunction "P$2_2") (pintype "passive"))
      (node (ref "IC5") (pin "4") (pinfunction "F_4") (pintype "tri_state"))
      (node (ref "R32") (pin "1") (pinfunction "1_1") (pintype "passive"))
    )
    (net (code "21") (name "BTN7_LED1") (class "Default")
      (node (ref "BTN7") (pin "LED1+") (pinfunction "LED1+_LED1+") (pintype "passive"))
      (node (ref "IC1") (pin "6") (pinfunction "QG_6") (pintype "tri_state"))
    )
    (net (code "22") (name "BTN7_LED2") (class "Default")
      (node (ref "BTN7") (pin "LED2+") (pinfunction "LED2+_LED2+") (pintype "passive"))
      (node (ref "IC1") (pin "7") (pinfunction "QH_7") (pintype "tri_state"))
    )
    (net (code "23") (name "BTN8") (class "Default")
      (node (ref "BTN8") (pin "SW3") (pinfunction "SW2_A_SW3") (pintype "passive"))
      (node (ref "BTN8") (pin "SW4") (pinfunction "SW2_B_SW4") (pintype "passive"))
      (node (ref "C24") (pin "2") (pinfunction "P$2_2") (pintype "passive"))
      (node (ref "IC5") (pin "3") (pinfunction "E_3") (pintype "tri_state"))
      (node (ref "R33") (pin "1") (pinfunction "1_1") (pintype "passive"))
    )
    (net (code "24") (name "BTN8_LED1") (class "Default")
      (node (ref "BTN8") (pin "LED1+") (pinfunction "LED1+_LED1+") (pintype "passive"))
      (node (ref "IC1") (pin "5") (pinfunction "QF_5") (pintype "tri_state"))
    )
    (net (code "25") (name "BTN8_LED2") (class "Default")
      (node (ref "BTN8") (pin "LED2+") (pinfunction "LED2+_LED2+") (pintype "passive"))
      (node (ref "IC1") (pin "15") (pinfunction "QA_15") (pintype "tri_state"))
    )
    (net (code "26") (name "CAN_H") (class "Default")
      (node (ref "BUS1") (pin "P$3") (pinfunction "1_P$3") (pintype "passive"))
      (node (ref "BUS2") (pin "P$3") (pinfunction "1_P$3") (pintype "passive"))
      (node (ref "D2") (pin "7") (pinfunction "CANH_7") (pintype "bidirectional"))
      (node (ref "TERM") (pin "3") (pinfunction "3_3") (pintype "passive"))
    )
    (net (code "27") (name "CAN_L") (class "Default")
      (node (ref "BUS1") (pin "P$2") (pinfunction "1_P$2") (pintype "passive"))
      (node (ref "BUS2") (pin "P$2") (pinfunction "1_P$2") (pintype "passive"))
      (node (ref "D2") (pin "6") (pinfunction "CANL_6") (pintype "bidirectional"))
      (node (ref "TERM") (pin "1") (pinfunction "1_1") (pintype "passive"))
    )
    (net (code "28") (name "CAN_RX") (class "Default")
      (node (ref "D2") (pin "4") (pinfunction "RXD_4") (pintype "output"))
      (node (ref "R14") (pin "1") (pinfunction "1_1") (pintype "passive"))
    )
    (net (code "29") (name "CAN_TX") (class "Default")
      (node (ref "D2") (pin "1") (pinfunction "TXD_1") (pintype "input"))
      (node (ref "R13") (pin "1") (pinfunction "1_1") (pintype "passive"))
    )
    (net (code "30") (name "CAN_VREF") (class "Default")
      (node (ref "C16") (pin "2") (pinfunction "P$2_2") (pintype "passive"))
      (node (ref "D2") (pin "5") (pinfunction "VREF_5") (pintype "output"))
      (node (ref "R3") (pin "2") (pinfunction "2_2") (pintype "passive"))
      (node (ref "R7") (pin "1") (pinfunction "1_1") (pintype "passive"))
    )
    (net (code "31") (name "DIN_4") (class "Default")
      (node (ref "IC4") (pin "14") (pinfunction "D_14") (pintype "tri_state"))
      (node (ref "R5") (pin "1") (pinfunction "1_1") (pintype "passive"))
    )
    (net (code "32") (name "DIN_8") (class "Default")
      (node (ref "IC4") (pin "6") (pinfunction "H_6") (pintype "tri_state"))
      (node (ref "R9") (pin "1") (pinfunction "1_1") (pintype "passive"))
    )
    (net (code "33") (name "FADER") (class "Default")
      (node (ref "C42") (pin "2") (pinfunction "P$2_2") (pintype "passive"))
      (node (ref "CPU1") (pin "22") (pinfunction "PA6/SPI1_MISO_22") (pintype "bidirectional"))
      (node (ref "FADER1") (pin "P2") (pinfunction "S_P2") (pintype "passive"))
    )
    (net (code "34") (name "GND") (class "Default")
      (node (ref "BTN1") (pin "SW1") (pinfunction "SW1_A_SW1") (pintype "passive"))
      (node (ref "BTN1") (pin "SW2") (pinfunction "SW1_B_SW2") (pintype "passive"))
      (node (ref "BTN2") (pin "SW1") (pinfunction "SW1_A_SW1") (pintype "passive"))
      (node (ref "BTN2") (pin "SW2") (pinfunction "SW1_B_SW2") (pintype "passive"))
      (node (ref "BTN3") (pin "SW1") (pinfunction "SW1_A_SW1") (pintype "passive"))
      (node (ref "BTN3") (pin "SW2") (pinfunction "SW1_B_SW2") (pintype "passive"))
      (node (ref "BTN4") (pin "SW1") (pinfunction "SW1_A_SW1") (pintype "passive"))
      (node (ref "BTN4") (pin "SW2") (pinfunction "SW1_B_SW2") (pintype "passive"))
      (node (ref "BTN5") (pin "SW1") (pinfunction "SW1_A_SW1") (pintype "passive"))
      (node (ref "BTN5") (pin "SW2") (pinfunction "SW1_B_SW2") (pintype "passive"))
      (node (ref "BTN6") (pin "SW1") (pinfunction "SW1_A_SW1") (pintype "passive"))
      (node (ref "BTN6") (pin "SW2") (pinfunction "SW1_B_SW2") (pintype "passive"))
      (node (ref "BTN7") (pin "SW1") (pinfunction "SW1_A_SW1") (pintype "passive"))
      (node (ref "BTN7") (pin "SW2") (pinfunction "SW1_B_SW2") (pintype "passive"))
      (node (ref "BTN8") (pin "SW1") (pinfunction "SW1_A_SW1") (pintype "passive"))
      (node (ref "BTN8") (pin "SW2") (pinfunction "SW1_B_SW2") (pintype "passive"))
      (node (ref "BUS1") (pin "P$4") (pinfunction "1_P$4") (pintype "passive"))
      (node (ref "BUS2") (pin "P$4") (pinfunction "1_P$4") (pintype "passive"))
      (node (ref "C1") (pin "1") (pinfunction "P$1_1") (pintype "passive"))
      (node (ref "C10") (pin "2") (pinfunction "P$2_2") (pintype "passive"))
      (node (ref "C11") (pin "2") (pinfunction "P$2_2") (pintype "passive"))
      (node (ref "C12") (pin "1") (pinfunction "P$1_1") (pintype "passive"))
      (node (ref "C13") (pin "2") (pinfunction "P$2_2") (pintype "passive"))
      (node (ref "C14") (pin "1") (pinfunction "P$1_1") (pintype "passive"))
      (node (ref "C15") (pin "1") (pinfunction "1_1") (pintype "passive"))
      (node (ref "C16") (pin "1") (pinfunction "P$1_1") (pintype "passive"))
      (node (ref "C17") (pin "1") (pinfunction "1_1") (pintype "passive"))
      (node (ref "C18") (pin "1") (pinfunction "1_1") (pintype "passive"))
      (node (ref "C19") (pin "2") (pinfunction "P$2_2") (pintype "passive"))
      (node (ref "C2") (pin "2") (pinfunction "P$2_2") (pintype "passive"))
      (node (ref "C20") (pin "1") (pinfunction "P$1_1") (pintype "passive"))
      (node (ref "C21") (pin "1") (pinfunction "P$1_1") (pintype "passive"))
      (node (ref "C22") (pin "1") (pinfunction "P$1_1") (pintype "passive"))
      (node (ref "C23") (pin "1") (pinfunction "P$1_1") (pintype "passive"))
      (node (ref "C24") (pin "1") (pinfunction "P$1_1") (pintype "passive"))
      (node (ref "C25") (pin "1") (pinfunction "P$1_1") (pintype "passive"))
      (node (ref "C26") (pin "1") (pinfunction "P$1_1") (pintype "passive"))
      (node (ref "C27") (pin "2") (pinfunction "P$2_2") (pintype "passive"))
      (node (ref "C28") (pin "2") (pinfunction "P$2_2") (pintype "passive"))
      (node (ref "C29") (pin "2") (pinfunction "P$2_2") (pintype "passive"))
      (node (ref "C3") (pin "1") (pinfunction "P$1_1") (pintype "passive"))
      (node (ref "C30") (pin "2") (pinfunction "P$2_2") (pintype "passive"))
      (node (ref "C31") (pin "1") (pinfunction "P$1_1") (pintype "passive"))
      (node (ref "C32") (pin "1") (pinfunction "P$1_1") (pintype "passive"))
      (node (ref "C33") (pin "1") (pinfunction "P$1_1") (pintype "passive"))
      (node (ref "C34") (pin "1") (pinfunction "P$1_1") (pintype "passive"))
      (node (ref "C35") (pin "1") (pinfunction "P$1_1") (pintype "passive"))
      (node (ref "C36") (pin "1") (pinfunction "P$1_1") (pintype "passive"))
      (node (ref "C37") (pin "1") (pinfunction "P$1_1") (pintype "passive"))
      (node (ref "C38") (pin "1") (pinfunction "P$1_1") (pintype "passive"))
      (node (ref "C39") (pin "1") (pinfunction "P$1_1") (pintype "passive"))
      (node (ref "C4") (pin "1") (pinfunction "P$1_1") (pintype "passive"))
      (node (ref "C40") (pin "1") (pinfunction "P$1_1") (pintype "passive"))
      (node (ref "C42") (pin "1") (pinfunction "P$1_1") (pintype "passive"))
      (node (ref "C43") (pin "1") (pinfunction "P$1_1") (pintype "passive"))
      (node (ref "C44") (pin "1") (pinfunction "P$1_1") (pintype "passive"))
      (node (ref "C45") (pin "1") (pinfunction "P$1_1") (pintype "passive"))
      (node (ref "C46") (pin "1") (pinfunction "P$1_1") (pintype "passive"))
      (node (ref "C47") (pin "1") (pinfunction "P$1_1") (pintype "passive"))
      (node (ref "C48") (pin "1") (pinfunction "P$1_1") (pintype "passive"))
      (node (ref "C49") (pin "1") (pinfunction "P$1_1") (pintype "passive"))
      (node (ref "C5") (pin "1") (pinfunction "P$1_1") (pintype "passive"))
      (node (ref "C6") (pin "1") (pinfunction "P$1_1") (pintype "passive"))
      (node (ref "C7") (pin "2") (pinfunction "P$2_2") (pintype "passive"))
      (node (ref "C8") (pin "2") (pinfunction "P$2_2") (pintype "passive"))
      (node (ref "C9") (pin "1") (pinfunction "P$1_1") (pintype "passive"))
      (node (ref "CPU1") (pin "12") (pinfunction "VSSA_12") (pintype "bidirectional"))
      (node (ref "CPU1") (pin "18") (pinfunction "VSS1_18") (pintype "bidirectional"))
      (node (ref "CPU1") (pin "63") (pinfunction "VSS2_63") (pintype "bidirectional"))
      (node (ref "D2") (pin "2") (pinfunction "GND_2") (pintype "power_in"))
      (node (ref "FADER1") (pin "P1") (pinfunction "A_P1") (pintype "passive"))
      (node (ref "IC1") (pin "13") (pinfunction "G_13") (pintype "input"))
      (node (ref "IC1") (pin "8") (pinfunction "GND_8") (pintype "power_in"))
      (node (ref "IC2") (pin "13") (pinfunction "G_13") (pintype "input"))
      (node (ref "IC2") (pin "8") (pinfunction "GND_8") (pintype "power_in"))
      (node (ref "IC3") (pin "13") (pinfunction "G_13") (pintype "input"))
      (node (ref "IC3") (pin "8") (pinfunction "GND_8") (pintype "power_in"))
      (node (ref "IC4") (pin "15") (pinfunction "CLK_INH_15") (pintype "input"))
      (node (ref "IC4") (pin "8") (pinfunction "GND_8") (pintype "power_in"))
      (node (ref "IC5") (pin "15") (pinfunction "CLK_INH_15") (pintype "input"))
      (node (ref "IC5") (pin "8") (pinfunction "GND_8") (pintype "power_in"))
      (node (ref "LCD") (pin "GND") (pinfunction "GND_GND") (pintype "bidirectional"))
      (node (ref "LED") (pin "C") (pinfunction "C_C") (pintype "passive"))
      (node (ref "POT1") (pin "CCW") (pinfunction "CCW_CCW") (pintype "passive"))
      (node (ref "POT2") (pin "CCW") (pinfunction "CCW_CCW") (pintype "passive"))
      (node (ref "POT3") (pin "CCW") (pinfunction "CCW_CCW") (pintype "passive"))
      (node (ref "POT4") (pin "CCW") (pinfunction "CCW_CCW") (pintype "passive"))
      (node (ref "POT5") (pin "CCW") (pinfunction "CCW_CCW") (pintype "passive"))
      (node (ref "POT6") (pin "CCW") (pinfunction "CCW_CCW") (pintype "passive"))
      (node (ref "POT7") (pin "CCW") (pinfunction "CCW_CCW") (pintype "passive"))
      (node (ref "PWR") (pin "C") (pinfunction "C_C") (pintype "passive"))
      (node (ref "R10") (pin "2") (pinfunction "2_2") (pintype "passive"))
      (node (ref "R12") (pin "2") (pinfunction "2_2") (pintype "passive"))
      (node (ref "R18") (pin "2") (pinfunction "2_2") (pintype "passive"))
      (node (ref "R19") (pin "2") (pinfunction "2_2") (pintype "passive"))
      (node (ref "R20") (pin "2") (pinfunction "2_2") (pintype "passive"))
      (node (ref "R21") (pin "2") (pinfunction "2_2") (pintype "passive"))
      (node (ref "R22") (pin "2") (pinfunction "2_2") (pintype "passive"))
      (node (ref "R23") (pin "2") (pinfunction "2_2") (pintype "passive"))
      (node (ref "R24") (pin "2") (pinfunction "2_2") (pintype "passive"))
      (node (ref "R25") (pin "2") (pinfunction "2_2") (pintype "passive"))
      (node (ref "R26") (pin "2") (pinfunction "2_2") (pintype "passive"))
      (node (ref "R27") (pin "2") (pinfunction "2_2") (pintype "passive"))
      (node (ref "R28") (pin "2") (pinfunction "2_2") (pintype "passive"))
      (node (ref "R29") (pin "2") (pinfunction "2_2") (pintype "passive"))
      (node (ref "R47") (pin "1") (pinfunction "1_1") (pintype "passive"))
      (node (ref "R48") (pin "1") (pinfunction "1_1") (pintype "passive"))
      (node (ref "R49") (pin "1") (pinfunction "1_1") (pintype "passive"))
      (node (ref "R50") (pin "1") (pinfunction "1_1") (pintype "passive"))
      (node (ref "R51") (pin "1") (pinfunction "1_1") (pintype "passive"))
      (node (ref "R52") (pin "1") (pinfunction "1_1") (pintype "passive"))
      (node (ref "R53") (pin "1") (pinfunction "1_1") (pintype "passive"))
      (node (ref "R54") (pin "1") (pinfunction "1_1") (pintype "passive"))
      (node (ref "R55") (pin "1") (pinfunction "1_1") (pintype "passive"))
      (node (ref "R56") (pin "1") (pinfunction "1_1") (pintype "passive"))
      (node (ref "ROT1") (pin "C") (pinfunction "COMMON_C") (pintype "input"))
      (node (ref "ROT1") (pin "S1") (pinfunction "SW1_S1") (pintype "bidirectional"))
      (node (ref "ROT2") (pin "C") (pinfunction "COMMON_C") (pintype "input"))
      (node (ref "ROT2") (pin "S1") (pinfunction "SW1_S1") (pintype "bidirectional"))
      (node (ref "T1") (pin "E") (pinfunction "E_E") (pintype "passive"))
      (node (ref "T2") (pin "E") (pinfunction "E_E") (pintype "passive"))
      (node (ref "TC1") (pin "3") (pinfunction "3_3") (pintype "passive"))
      (node (ref "TC1") (pin "5") (pinfunction "5_5") (pintype "passive"))
      (node (ref "TC1") (pin "9") (pinfunction "9_9") (pintype "passive"))
      (node (ref "U1") (pin "1") (pinfunction "ADJ_1") (pintype "input"))
    )
    (net (code "35") (name "LCD_CLK") (class "Default")
      (node (ref "CPU1") (pin "55") (pinfunction "PB3/JTDO_55") (pintype "bidirectional"))
      (node (ref "LCD") (pin "CLK") (pinfunction "CLK_CLK") (pintype "bidirectional"))
    )
    (net (code "36") (name "LCD_CS") (class "Default")
      (node (ref "CPU1") (pin "58") (pinfunction "PB6_58") (pintype "bidirectional"))
      (node (ref "LCD") (pin "CS") (pinfunction "CS_CS") (pintype "bidirectional"))
    )
    (net (code "37") (name "LCD_DC") (class "Default")
      (node (ref "CPU1") (pin "59") (pinfunction "PB7_59") (pintype "bidirectional"))
      (node (ref "LCD") (pin "DC") (pinfunction "DC_DC") (pintype "bidirectional"))
    )
    (net (code "38") (name "LCD_MISO_UNUSED") (class "Default")
      (node (ref "CPU1") (pin "56") (pinfunction "PB4/JTRST_56") (pintype "bidirectional"))
    )
    (net (code "39") (name "LCD_MOSI") (class "Default")
      (node (ref "CPU1") (pin "57") (pinfunction "PB5_57") (pintype "bidirectional"))
      (node (ref "LCD") (pin "MOSI") (pinfunction "MOSI_MOSI") (pintype "bidirectional"))
    )
    (net (code "40") (name "LCD_RST") (class "Default")
      (node (ref "CPU1") (pin "54") (pinfunction "PD2/SDIO_CMD_54") (pintype "bidirectional"))
      (node (ref "LCD") (pin "RES") (pinfunction "RST_RES") (pintype "bidirectional"))
    )
    (net (code "41") (name "NRST") (class "Default")
      (node (ref "CPU1") (pin "7") (pinfunction "NRST_7") (pintype "bidirectional"))
      (node (ref "TC1") (pin "10") (pinfunction "10_10") (pintype "passive"))
    )
    (net (code "42") (name "Net-(BTN1-PadLED1-)") (class "Default")
      (node (ref "BTN1") (pin "LED1-") (pinfunction "LED1-_LED1-") (pintype "passive"))
      (node (ref "R8") (pin "1") (pinfunction "1_1") (pintype "passive"))
    )
    (net (code "43") (name "Net-(BTN2-PadLED1-)") (class "Default")
      (node (ref "BTN2") (pin "LED1-") (pinfunction "LED1-_LED1-") (pintype "passive"))
      (node (ref "R15") (pin "1") (pinfunction "1_1") (pintype "passive"))
    )
    (net (code "44") (name "Net-(BTN3-PadLED1-)") (class "Default")
      (node (ref "BTN3") (pin "LED1-") (pinfunction "LED1-_LED1-") (pintype "passive"))
      (node (ref "R20") (pin "1") (pinfunction "1_1") (pintype "passive"))
    )
    (net (code "45") (name "Net-(BTN3-PadLED2-)") (class "Default")
      (node (ref "BTN3") (pin "LED2-") (pinfunction "LED2-_LED2-") (pintype "passive"))
      (node (ref "R21") (pin "1") (pinfunction "1_1") (pintype "passive"))
    )
    (net (code "46") (name "Net-(BTN4-PadLED1-)") (class "Default")
      (node (ref "BTN4") (pin "LED1-") (pinfunction "LED1-_LED1-") (pintype "passive"))
      (node (ref "R22") (pin "1") (pinfunction "1_1") (pintype "passive"))
    )
    (net (code "47") (name "Net-(BTN4-PadLED2-)") (class "Default")
      (node (ref "BTN4") (pin "LED2-") (pinfunction "LED2-_LED2-") (pintype "passive"))
      (node (ref "R23") (pin "1") (pinfunction "1_1") (pintype "passive"))
    )
    (net (code "48") (name "Net-(BTN5-PadLED1-)") (class "Default")
      (node (ref "BTN5") (pin "LED1-") (pinfunction "LED1-_LED1-") (pintype "passive"))
      (node (ref "R28") (pin "1") (pinfunction "1_1") (pintype "passive"))
    )
    (net (code "49") (name "Net-(BTN5-PadLED2-)") (class "Default")
      (node (ref "BTN5") (pin "LED2-") (pinfunction "LED2-_LED2-") (pintype "passive"))
      (node (ref "R29") (pin "1") (pinfunction "1_1") (pintype "passive"))
    )
    (net (code "50") (name "Net-(BTN6-PadLED1-)") (class "Default")
      (node (ref "BTN6") (pin "LED1-") (pinfunction "LED1-_LED1-") (pintype "passive"))
      (node (ref "R18") (pin "1") (pinfunction "1_1") (pintype "passive"))
    )
    (net (code "51") (name "Net-(BTN6-PadLED2-)") (class "Default")
      (node (ref "BTN6") (pin "LED2-") (pinfunction "LED2-_LED2-") (pintype "passive"))
      (node (ref "R19") (pin "1") (pinfunction "1_1") (pintype "passive"))
    )
    (net (code "52") (name "Net-(BTN7-PadLED1-)") (class "Default")
      (node (ref "BTN7") (pin "LED1-") (pinfunction "LED1-_LED1-") (pintype "passive"))
      (node (ref "R24") (pin "1") (pinfunction "1_1") (pintype "passive"))
    )
    (net (code "53") (name "Net-(BTN7-PadLED2-)") (class "Default")
      (node (ref "BTN7") (pin "LED2-") (pinfunction "LED2-_LED2-") (pintype "passive"))
      (node (ref "R25") (pin "1") (pinfunction "1_1") (pintype "passive"))
    )
    (net (code "54") (name "Net-(BTN8-PadLED1-)") (class "Default")
      (node (ref "BTN8") (pin "LED1-") (pinfunction "LED1-_LED1-") (pintype "passive"))
      (node (ref "R26") (pin "1") (pinfunction "1_1") (pintype "passive"))
    )
    (net (code "55") (name "Net-(BTN8-PadLED2-)") (class "Default")
      (node (ref "BTN8") (pin "LED2-") (pinfunction "LED2-_LED2-") (pintype "passive"))
      (node (ref "R27") (pin "1") (pinfunction "1_1") (pintype "passive"))
    )
    (net (code "56") (name "Net-(C5-P$2)") (class "Default")
      (node (ref "C5") (pin "2") (pinfunction "P$2_2") (pintype "passive"))
      (node (ref "CPU1") (pin "5") (pinfunction "PH0_5") (pintype "bidirectional"))
      (node (ref "U$19") (pin "P$2") (pinfunction "2_P$2") (pintype "passive"))
    )
    (net (code "57") (name "Net-(C6-P$2)") (class "Default")
      (node (ref "C6") (pin "2") (pinfunction "P$2_2") (pintype "passive"))
      (node (ref "CPU1") (pin "6") (pinfunction "PH1_6") (pintype "bidirectional"))
      (node (ref "U$19") (pin "P$1") (pinfunction "1_P$1") (pintype "passive"))
    )
    (net (code "58") (name "Net-(C7-P$1)") (class "Default")
      (node (ref "C7") (pin "1") (pinfunction "P$1_1") (pintype "passive"))
      (node (ref "CPU1") (pin "31") (pinfunction "VCAP1_31") (pintype "bidirectional"))
    )
    (net (code "59") (name "Net-(C13-P$1)") (class "Default")
      (node (ref "C13") (pin "1") (pinfunction "P$1_1") (pintype "passive"))
      (node (ref "CPU1") (pin "47") (pinfunction "VCAP2_47") (pintype "bidirectional"))
    )
    (net (code "60") (name "Net-(CPU1-BOOT0)") (class "Default")
      (node (ref "CPU1") (pin "60") (pinfunction "BOOT0_60") (pintype "bidirectional"))
      (node (ref "R12") (pin "1") (pinfunction "1_1") (pintype "passive"))
    )
    (net (code "61") (name "Net-(CPU1-PB8)") (class "Default")
      (node (ref "CPU1") (pin "61") (pinfunction "PB8_61") (pintype "bidirectional"))
      (node (ref "R14") (pin "2") (pinfunction "2_2") (pintype "passive"))
    )
    (net (code "62") (name "Net-(CPU1-PB9)") (class "Default")
      (node (ref "CPU1") (pin "62") (pinfunction "PB9_62") (pintype "bidirectional"))
      (node (ref "R13") (pin "2") (pinfunction "2_2") (pintype "passive"))
    )
    (net (code "63") (name "Net-(CPU1-PC12{slash}SDIO_CLK)") (class "Default")
      (node (ref "CPU1") (pin "53") (pinfunction "PC12/SDIO_CLK_53") (pintype "bidirectional"))
      (node (ref "R2") (pin "2") (pinfunction "2_2") (pintype "passive"))
    )
    (net (code "64") (name "Net-(D1A-A)") (class "Default")
      (node (ref "D1") (pin "1") (pinfunction "A_1") (pintype "passive"))
      (node (ref "IC2") (pin "6") (pinfunction "QG_6") (pintype "tri_state"))
    )
    (net (code "65") (name "Net-(D1A-C)") (class "Default")
      (node (ref "D1") (pin "20") (pinfunction "C_20") (pintype "passive"))
      (node (ref "R56") (pin "2") (pinfunction "2_2") (pintype "passive"))
    )
    (net (code "66") (name "Net-(D1B-A)") (class "Default")
      (node (ref "D1") (pin "2") (pinfunction "A_2") (pintype "passive"))
      (node (ref "IC2") (pin "7") (pinfunction "QH_7") (pintype "tri_state"))
    )
    (net (code "67") (name "Net-(D1B-C)") (class "Default")
      (node (ref "D1") (pin "19") (pinfunction "C_19") (pintype "passive"))
      (node (ref "R55") (pin "2") (pinfunction "2_2") (pintype "passive"))
    )
    (net (code "68") (name "Net-(D1C-A)") (class "Default")
      (node (ref "D1") (pin "3") (pinfunction "A_3") (pintype "passive"))
      (node (ref "IC3") (pin "15") (pinfunction "QA_15") (pintype "tri_state"))
    )
    (net (code "69") (name "Net-(D1C-C)") (class "Default")
      (node (ref "D1") (pin "18") (pinfunction "C_18") (pintype "passive"))
      (node (ref "R54") (pin "2") (pinfunction "2_2") (pintype "passive"))
    )
    (net (code "70") (name "Net-(D1D-A)") (class "Default")
      (node (ref "D1") (pin "4") (pinfunction "A_4") (pintype "passive"))
      (node (ref "IC3") (pin "1") (pinfunction "QB_1") (pintype "tri_state"))
    )
    (net (code "71") (name "Net-(D1D-C)") (class "Default")
      (node (ref "D1") (pin "17") (pinfunction "C_17") (pintype "passive"))
      (node (ref "R53") (pin "2") (pinfunction "2_2") (pintype "passive"))
    )
    (net (code "72") (name "Net-(D1E-A)") (class "Default")
      (node (ref "D1") (pin "5") (pinfunction "A_5") (pintype "passive"))
      (node (ref "IC3") (pin "2") (pinfunction "QC_2") (pintype "tri_state"))
    )
    (net (code "73") (name "Net-(D1E-C)") (class "Default")
      (node (ref "D1") (pin "16") (pinfunction "C_16") (pintype "passive"))
      (node (ref "R52") (pin "2") (pinfunction "2_2") (pintype "passive"))
    )
    (net (code "74") (name "Net-(D1F-A)") (class "Default")
      (node (ref "D1") (pin "6") (pinfunction "A_6") (pintype "passive"))
      (node (ref "IC3") (pin "3") (pinfunction "QD_3") (pintype "tri_state"))
    )
    (net (code "75") (name "Net-(D1F-C)") (class "Default")
      (node (ref "D1") (pin "15") (pinfunction "C_15") (pintype "passive"))
      (node (ref "R51") (pin "2") (pinfunction "2_2") (pintype "passive"))
    )
    (net (code "76") (name "Net-(D1G-A)") (class "Default")
      (node (ref "D1") (pin "7") (pinfunction "A_7") (pintype "passive"))
      (node (ref "IC3") (pin "4") (pinfunction "QE_4") (pintype "tri_state"))
    )
    (net (code "77") (name "Net-(D1G-C)") (class "Default")
      (node (ref "D1") (pin "14") (pinfunction "C_14") (pintype "passive"))
      (node (ref "R50") (pin "2") (pinfunction "2_2") (pintype "passive"))
    )
    (net (code "78") (name "Net-(D1H-A)") (class "Default")
      (node (ref "D1") (pin "8") (pinfunction "A_8") (pintype "passive"))
      (node (ref "IC3") (pin "5") (pinfunction "QF_5") (pintype "tri_state"))
    )
    (net (code "79") (name "Net-(D1H-C)") (class "Default")
      (node (ref "D1") (pin "13") (pinfunction "C_13") (pintype "passive"))
      (node (ref "R49") (pin "2") (pinfunction "2_2") (pintype "passive"))
    )
    (net (code "80") (name "Net-(D1I-A)") (class "Default")
      (node (ref "D1") (pin "9") (pinfunction "A_9") (pintype "passive"))
      (node (ref "IC3") (pin "6") (pinfunction "QG_6") (pintype "tri_state"))
    )
    (net (code "81") (name "Net-(D1I-C)") (class "Default")
      (node (ref "D1") (pin "12") (pinfunction "C_12") (pintype "passive"))
      (node (ref "R48") (pin "2") (pinfunction "2_2") (pintype "passive"))
    )
    (net (code "82") (name "Net-(D1J-A)") (class "Default")
      (node (ref "D1") (pin "10") (pinfunction "A_10") (pintype "passive"))
      (node (ref "IC3") (pin "7") (pinfunction "QH_7") (pintype "tri_state"))
    )
    (net (code "83") (name "Net-(D1J-C)") (class "Default")
      (node (ref "D1") (pin "11") (pinfunction "C_11") (pintype "passive"))
      (node (ref "R47") (pin "2") (pinfunction "2_2") (pintype "passive"))
    )
    (net (code "84") (name "Net-(D2-RS)") (class "Default")
      (node (ref "D2") (pin "8") (pinfunction "RS_8") (pintype "input"))
      (node (ref "R10") (pin "1") (pinfunction "1_1") (pintype "passive"))
    )
    (net (code "85") (name "Net-(IC1-SER)") (class "Default")
      (node (ref "IC1") (pin "14") (pinfunction "SER_14") (pintype "input"))
      (node (ref "IC2") (pin "9") (pinfunction "QH*_9") (pintype "tri_state"))
    )
    (net (code "86") (name "Net-(IC2-SER)") (class "Default")
      (node (ref "IC2") (pin "14") (pinfunction "SER_14") (pintype "input"))
      (node (ref "IC3") (pin "9") (pinfunction "QH*_9") (pintype "tri_state"))
    )
    (net (code "87") (name "Net-(IC4-SER)") (class "Default")
      (node (ref "IC4") (pin "10") (pinfunction "SER_10") (pintype "input"))
      (node (ref "IC5") (pin "9") (pinfunction "QH_9") (pintype "tri_state"))
      (node (ref "R38") (pin "1") (pinfunction "1_1") (pintype "passive"))
    )
    (net (code "88") (name "Net-(IC5-SER)") (class "Default")
      (node (ref "IC5") (pin "10") (pinfunction "SER_10") (pintype "input"))
      (node (ref "R1") (pin "1") (pinfunction "1_1") (pintype "passive"))
    )
    (net (code "89") (name "Net-(LED-PadA)") (class "Default")
      (node (ref "LED") (pin "A") (pinfunction "A_A") (pintype "passive"))
      (node (ref "R2") (pin "1") (pinfunction "1_1") (pintype "passive"))
    )
    (net (code "90") (name "Net-(PWR-PadA)") (class "Default")
      (node (ref "PWR") (pin "A") (pinfunction "A_A") (pintype "passive"))
      (node (ref "R17") (pin "1") (pinfunction "1_1") (pintype "passive"))
    )
    (net (code "91") (name "Net-(R3-Pad1)") (class "Default")
      (node (ref "R3") (pin "1") (pinfunction "1_1") (pintype "passive"))
      (node (ref "TERM") (pin "4") (pinfunction "4_4") (pintype "passive"))
    )
    (net (code "92") (name "Net-(R7-Pad2)") (class "Default")
      (node (ref "R7") (pin "2") (pinfunction "2_2") (pintype "passive"))
      (node (ref "TERM") (pin "2") (pinfunction "2_2") (pintype "passive"))
    )
    (net (code "93") (name "Net-(R8-Pad2)") (class "Default")
      (node (ref "R8") (pin "2") (pinfunction "2_2") (pintype "passive"))
      (node (ref "T1") (pin "C") (pinfunction "C_C") (pintype "passive"))
    )
    (net (code "94") (name "Net-(R11-Pad2)") (class "Default")
      (node (ref "R11") (pin "2") (pinfunction "2_2") (pintype "passive"))
      (node (ref "T1") (pin "B") (pinfunction "B_B") (pintype "passive"))
    )
    (net (code "95") (name "Net-(R15-Pad2)") (class "Default")
      (node (ref "R15") (pin "2") (pinfunction "2_2") (pintype "passive"))
      (node (ref "T2") (pin "C") (pinfunction "C_C") (pintype "passive"))
    )
    (net (code "96") (name "Net-(R16-Pad2)") (class "Default")
      (node (ref "R16") (pin "2") (pinfunction "2_2") (pintype "passive"))
      (node (ref "T2") (pin "B") (pinfunction "B_B") (pintype "passive"))
    )
    (net (code "97") (name "Net-(ROT1-CH_A)") (class "Default")
      (node (ref "R39") (pin "2") (pinfunction "2_2") (pintype "passive"))
      (node (ref "R41") (pin "2") (pinfunction "2_2") (pintype "passive"))
      (node (ref "ROT1") (pin "A") (pinfunction "CH_A_A") (pintype "output"))
    )
    (net (code "98") (name "Net-(ROT1-CH_B)") (class "Default")
      (node (ref "R40") (pin "2") (pinfunction "2_2") (pintype "passive"))
      (node (ref "R42") (pin "2") (pinfunction "2_2") (pintype "passive"))
      (node (ref "ROT1") (pin "B") (pinfunction "CH_B_B") (pintype "output"))
    )
    (net (code "99") (name "Net-(ROT2-CH_A)") (class "Default")
      (node (ref "R43") (pin "2") (pinfunction "2_2") (pintype "passive"))
      (node (ref "R45") (pin "2") (pinfunction "2_2") (pintype "passive"))
      (node (ref "ROT2") (pin "A") (pinfunction "CH_A_A") (pintype "output"))
    )
    (net (code "100") (name "Net-(ROT2-CH_B)") (class "Default")
      (node (ref "R44") (pin "2") (pinfunction "2_2") (pintype "passive"))
      (node (ref "R46") (pin "2") (pinfunction "2_2") (pintype "passive"))
      (node (ref "ROT2") (pin "B") (pinfunction "CH_B_B") (pintype "output"))
    )
    (net (code "101") (name "POT1") (class "Default")
      (node (ref "C46") (pin "2") (pinfunction "P$2_2") (pintype "passive"))
      (node (ref "CPU1") (pin "14") (pinfunction "PA0_14") (pintype "bidirectional"))
      (node (ref "POT1") (pin "CENTER") (pinfunction "WIPER_CENTER") (pintype "passive"))
    )
    (net (code "102") (name "POT2") (class "Default")
      (node (ref "C49") (pin "2") (pinfunction "P$2_2") (pintype "passive"))
      (node (ref "CPU1") (pin "17") (pinfunction "PA3/UART2_RX_17") (pintype "bidirectional"))
      (node (ref "POT2") (pin "CENTER") (pinfunction "WIPER_CENTER") (pintype "passive"))
    )
    (net (code "103") (name "POT3") (class "Default")
      (node (ref "C45") (pin "2") (pinfunction "P$2_2") (pintype "passive"))
      (node (ref "CPU1") (pin "15") (pinfunction "PA1_15") (pintype "bidirectional"))
      (node (ref "POT3") (pin "CENTER") (pinfunction "WIPER_CENTER") (pintype "passive"))
    )
    (net (code "104") (name "POT4") (class "Default")
      (node (ref "C48") (pin "2") (pinfunction "P$2_2") (pintype "passive"))
      (node (ref "CPU1") (pin "16") (pinfunction "PA2/UART2_TX_16") (pintype "bidirectional"))
      (node (ref "POT4") (pin "CENTER") (pinfunction "WIPER_CENTER") (pintype "passive"))
    )
    (net (code "105") (name "POT5") (class "Default")
      (node (ref "C44") (pin "2") (pinfunction "P$2_2") (pintype "passive"))
      (node (ref "CPU1") (pin "23") (pinfunction "PA7/SPI1_MOSI_23") (pintype "bidirectional"))
      (node (ref "POT5") (pin "CENTER") (pinfunction "WIPER_CENTER") (pintype "passive"))
    )
    (net (code "106") (name "POT6") (class "Default")
      (node (ref "C47") (pin "2") (pinfunction "P$2_2") (pintype "passive"))
      (node (ref "CPU1") (pin "20") (pinfunction "PA4/SPI1_NSS_20") (pintype "bidirectional"))
      (node (ref "POT6") (pin "CENTER") (pinfunction "WIPER_CENTER") (pintype "passive"))
    )
    (net (code "107") (name "POT7") (class "Default")
      (node (ref "C43") (pin "2") (pinfunction "P$2_2") (pintype "passive"))
      (node (ref "CPU1") (pin "21") (pinfunction "PA5/SPI1_SCK_21") (pintype "bidirectional"))
      (node (ref "POT7") (pin "CENTER") (pinfunction "WIPER_CENTER") (pintype "passive"))
    )
    (net (code "108") (name "ROT1_A") (class "Default")
      (node (ref "C27") (pin "1") (pinfunction "P$1_1") (pintype "passive"))
      (node (ref "IC4") (pin "4") (pinfunction "F_4") (pintype "tri_state"))
      (node (ref "R39") (pin "1") (pinfunction "1_1") (pintype "passive"))
    )
    (net (code "109") (name "ROT1_B") (class "Default")
      (node (ref "C28") (pin "1") (pinfunction "P$1_1") (pintype "passive"))
      (node (ref "IC4") (pin "5") (pinfunction "G_5") (pintype "tri_state"))
      (node (ref "R40") (pin "1") (pinfunction "1_1") (pintype "passive"))
    )
    (net (code "110") (name "ROT1_SW") (class "Default")
      (node (ref "IC4") (pin "3") (pinfunction "E_3") (pintype "tri_state"))
      (node (ref "R6") (pin "1") (pinfunction "1_1") (pintype "passive"))
      (node (ref "ROT1") (pin "S2") (pinfunction "SW2_S2") (pintype "bidirectional"))
    )
    (net (code "111") (name "ROT2_A") (class "Default")
      (node (ref "C29") (pin "1") (pinfunction "P$1_1") (pintype "passive"))
      (node (ref "IC4") (pin "11") (pinfunction "A_11") (pintype "tri_state"))
      (node (ref "R43") (pin "1") (pinfunction "1_1") (pintype "passive"))
    )
    (net (code "112") (name "ROT2_B") (class "Default")
      (node (ref "C30") (pin "1") (pinfunction "P$1_1") (pintype "passive"))
      (node (ref "IC4") (pin "12") (pinfunction "B_12") (pintype "tri_state"))
      (node (ref "R44") (pin "1") (pinfunction "1_1") (pintype "passive"))
    )
    (net (code "113") (name "ROT2_SW") (class "Default")
      (node (ref "IC4") (pin "13") (pinfunction "C_13") (pintype "tri_state"))
      (node (ref "R4") (pin "1") (pinfunction "1_1") (pintype "passive"))
      (node (ref "ROT2") (pin "S2") (pinfunction "SW2_S2") (pintype "bidirectional"))
    )
    (net (code "114") (name "SPI2_CLK") (class "Default")
      (node (ref "CPU1") (pin "34") (pinfunction "PB13/I2S2_CK_34") (pintype "bidirectional"))
      (node (ref "IC1") (pin "11") (pinfunction "SCK_11") (pintype "input"))
      (node (ref "IC2") (pin "11") (pinfunction "SCK_11") (pintype "input"))
      (node (ref "IC3") (pin "11") (pinfunction "SCK_11") (pintype "input"))
      (node (ref "IC4") (pin "2") (pinfunction "CLK_2") (pintype "input"))
      (node (ref "IC5") (pin "2") (pinfunction "CLK_2") (pintype "input"))
    )
    (net (code "115") (name "SPI2_MISO") (class "Default")
      (node (ref "CPU1") (pin "35") (pinfunction "PB14/I2S2_XD_35") (pintype "bidirectional"))
      (node (ref "IC4") (pin "9") (pinfunction "QH_9") (pintype "tri_state"))
    )
    (net (code "116") (name "SPI2_MOSI") (class "Default")
      (node (ref "CPU1") (pin "36") (pinfunction "PB15/I2S2_SD_36") (pintype "bidirectional"))
      (node (ref "IC3") (pin "14") (pinfunction "SER_14") (pintype "input"))
    )
    (net (code "117") (name "SPI2_RC1") (class "Default")
      (node (ref "CPU1") (pin "11") (pinfunction "PC3_11") (pintype "bidirectional"))
      (node (ref "IC1") (pin "12") (pinfunction "RCK_12") (pintype "input"))
      (node (ref "IC2") (pin "12") (pinfunction "RCK_12") (pintype "input"))
      (node (ref "IC3") (pin "12") (pinfunction "RCK_12") (pintype "input"))
    )
    (net (code "118") (name "SPI2_RC2") (class "Default")
      (node (ref "CPU1") (pin "10") (pinfunction "PC2_10") (pintype "bidirectional"))
      (node (ref "IC4") (pin "1") (pinfunction "SH/~{LD}_1") (pintype "input"))
      (node (ref "IC5") (pin "1") (pinfunction "SH/~{LD}_1") (pintype "input"))
    )
    (net (code "119") (name "SWCK") (class "Default")
      (node (ref "CPU1") (pin "49") (pinfunction "PA14/JTCK_49") (pintype "bidirectional"))
      (node (ref "TC1") (pin "4") (pinfunction "4_4") (pintype "passive"))
    )
    (net (code "120") (name "SWDIO") (class "Default")
      (node (ref "CPU1") (pin "46") (pinfunction "PA13/JTMS_46") (pintype "bidirectional"))
      (node (ref "TC1") (pin "2") (pinfunction "2_2") (pintype "passive"))
    )
    (net (code "121") (name "UART_RX") (class "Default")
      (node (ref "CPU1") (pin "52") (pinfunction "PC11/SDIO_D3_52") (pintype "bidirectional"))
      (node (ref "TC1") (pin "8") (pinfunction "8_8") (pintype "passive"))
    )
    (net (code "122") (name "UART_TX") (class "Default")
      (node (ref "CPU1") (pin "51") (pinfunction "PC10/SDIO_D2_51") (pintype "bidirectional"))
      (node (ref "TC1") (pin "6") (pinfunction "6_6") (pintype "passive"))
    )
    (net (code "123") (name "unconnected-(CPU1-PA8-Pad41)") (class "Default")
      (node (ref "CPU1") (pin "41") (pinfunction "PA8_41") (pintype "bidirectional"))
    )
    (net (code "124") (name "unconnected-(CPU1-PA9{slash}UART1_TX-Pad42)") (class "Default")
      (node (ref "CPU1") (pin "42") (pinfunction "PA9/UART1_TX_42") (pintype "bidirectional"))
    )
    (net (code "125") (name "unconnected-(CPU1-PA10{slash}UART1_RX-Pad43)") (class "Default")
      (node (ref "CPU1") (pin "43") (pinfunction "PA10/UART1_RX_43") (pintype "bidirectional"))
    )
    (net (code "126") (name "unconnected-(CPU1-PA11-Pad44)") (class "Default")
      (node (ref "CPU1") (pin "44") (pinfunction "PA11_44") (pintype "bidirectional"))
    )
    (net (code "127") (name "unconnected-(CPU1-PA12-Pad45)") (class "Default")
      (node (ref "CPU1") (pin "45") (pinfunction "PA12_45") (pintype "bidirectional"))
    )
    (net (code "128") (name "unconnected-(CPU1-PA15{slash}JTDI-Pad50)") (class "Default")
      (node (ref "CPU1") (pin "50") (pinfunction "PA15/JTDI_50") (pintype "bidirectional"))
    )
    (net (code "129") (name "unconnected-(CPU1-PB0-Pad26)") (class "Default")
      (node (ref "CPU1") (pin "26") (pinfunction "PB0_26") (pintype "bidirectional"))
    )
    (net (code "130") (name "unconnected-(CPU1-PB1-Pad27)") (class "Default")
      (node (ref "CPU1") (pin "27") (pinfunction "PB1_27") (pintype "bidirectional"))
    )
    (net (code "131") (name "unconnected-(CPU1-PB2-BOOT1-Pad28)") (class "Default")
      (node (ref "CPU1") (pin "28") (pinfunction "PB2-BOOT1_28") (pintype "bidirectional"))
    )
    (net (code "132") (name "unconnected-(CPU1-PB10-Pad29)") (class "Default")
      (node (ref "CPU1") (pin "29") (pinfunction "PB10_29") (pintype "bidirectional"))
    )
    (net (code "133") (name "unconnected-(CPU1-PB11-Pad30)") (class "Default")
      (node (ref "CPU1") (pin "30") (pinfunction "PB11_30") (pintype "bidirectional"))
    )
    (net (code "134") (name "unconnected-(CPU1-PB12{slash}I2S2_WS-Pad33)") (class "Default")
      (node (ref "CPU1") (pin "33") (pinfunction "PB12/I2S2_WS_33") (pintype "bidirectional"))
    )
    (net (code "135") (name "unconnected-(CPU1-PC0-Pad8)") (class "Default")
      (node (ref "CPU1") (pin "8") (pinfunction "PC0_8") (pintype "bidirectional"))
    )
    (net (code "136") (name "unconnected-(CPU1-PC1-Pad9)") (class "Default")
      (node (ref "CPU1") (pin "9") (pinfunction "PC1_9") (pintype "bidirectional"))
    )
    (net (code "137") (name "unconnected-(CPU1-PC4-Pad24)") (class "Default")
      (node (ref "CPU1") (pin "24") (pinfunction "PC4_24") (pintype "bidirectional"))
    )
    (net (code "138") (name "unconnected-(CPU1-PC5-Pad25)") (class "Default")
      (node (ref "CPU1") (pin "25") (pinfunction "PC5_25") (pintype "bidirectional"))
    )
    (net (code "139") (name "unconnected-(CPU1-PC6{slash}I2S2_MCK-Pad37)") (class "Default")
      (node (ref "CPU1") (pin "37") (pinfunction "PC6/I2S2_MCK_37") (pintype "bidirectional"))
    )
    (net (code "140") (name "unconnected-(CPU1-PC7-Pad38)") (class "Default")
      (node (ref "CPU1") (pin "38") (pinfunction "PC7_38") (pintype "bidirectional"))
    )
    (net (code "141") (name "unconnected-(CPU1-PC8{slash}SDIO_D0-Pad39)") (class "Default")
      (node (ref "CPU1") (pin "39") (pinfunction "PC8/SDIO_D0_39") (pintype "bidirectional"))
    )
    (net (code "142") (name "unconnected-(CPU1-PC9{slash}SDIO_D1-Pad40)") (class "Default")
      (node (ref "CPU1") (pin "40") (pinfunction "PC9/SDIO_D1_40") (pintype "bidirectional"))
    )
    (net (code "143") (name "unconnected-(CPU1-PC13-Pad2)") (class "Default")
      (node (ref "CPU1") (pin "2") (pinfunction "PC13_2") (pintype "bidirectional"))
    )
    (net (code "144") (name "unconnected-(CPU1-PC14-Pad3)") (class "Default")
      (node (ref "CPU1") (pin "3") (pinfunction "PC14_3") (pintype "bidirectional"))
    )
    (net (code "145") (name "unconnected-(CPU1-PC15-Pad4)") (class "Default")
      (node (ref "CPU1") (pin "4") (pinfunction "PC15_4") (pintype "bidirectional"))
    )
    (net (code "146") (name "unconnected-(IC1-QH*-Pad9)") (class "Default")
      (node (ref "IC1") (pin "9") (pinfunction "QH*_9") (pintype "tri_state"))
    )
    (net (code "147") (name "unconnected-(IC4-~{QH}-Pad7)") (class "Default")
      (node (ref "IC4") (pin "7") (pinfunction "~{QH}_7") (pintype "input"))
    )
    (net (code "148") (name "unconnected-(IC5-~{QH}-Pad7)") (class "Default")
      (node (ref "IC5") (pin "7") (pinfunction "~{QH}_7") (pintype "input"))
    )
    (net (code "149") (name "unconnected-(POT1-CHASSIS-Pad4)") (class "Default")
      (node (ref "POT1") (pin "4") (pinfunction "CHASSIS_4") (pintype "passive"))
    )
    (net (code "150") (name "unconnected-(POT2-CHASSIS-Pad4)") (class "Default")
      (node (ref "POT2") (pin "4") (pinfunction "CHASSIS_4") (pintype "passive"))
    )
    (net (code "151") (name "unconnected-(POT3-CHASSIS-Pad4)") (class "Default")
      (node (ref "POT3") (pin "4") (pinfunction "CHASSIS_4") (pintype "passive"))
    )
    (net (code "152") (name "unconnected-(POT4-CHASSIS-Pad4)") (class "Default")
      (node (ref "POT4") (pin "4") (pinfunction "CHASSIS_4") (pintype "passive"))
    )
    (net (code "153") (name "unconnected-(POT5-CHASSIS-Pad4)") (class "Default")
      (node (ref "POT5") (pin "4") (pinfunction "CHASSIS_4") (pintype "passive"))
    )
    (net (code "154") (name "unconnected-(POT6-CHASSIS-Pad4)") (class "Default")
      (node (ref "POT6") (pin "4") (pinfunction "CHASSIS_4") (pintype "passive"))
    )
    (net (code "155") (name "unconnected-(POT7-CHASSIS-Pad4)") (class "Default")
      (node (ref "POT7") (pin "4") (pinfunction "CHASSIS_4") (pintype "passive"))
    )
    (net (code "156") (name "unconnected-(TC1-Pad7)") (class "Default")
      (node (ref "TC1") (pin "7") (pinfunction "7_7") (pintype "passive"))
    )
  )
)
